# Cuttomized_Industrial_controller.net
KiCad netlist of a schematic drawn in Altium Designer
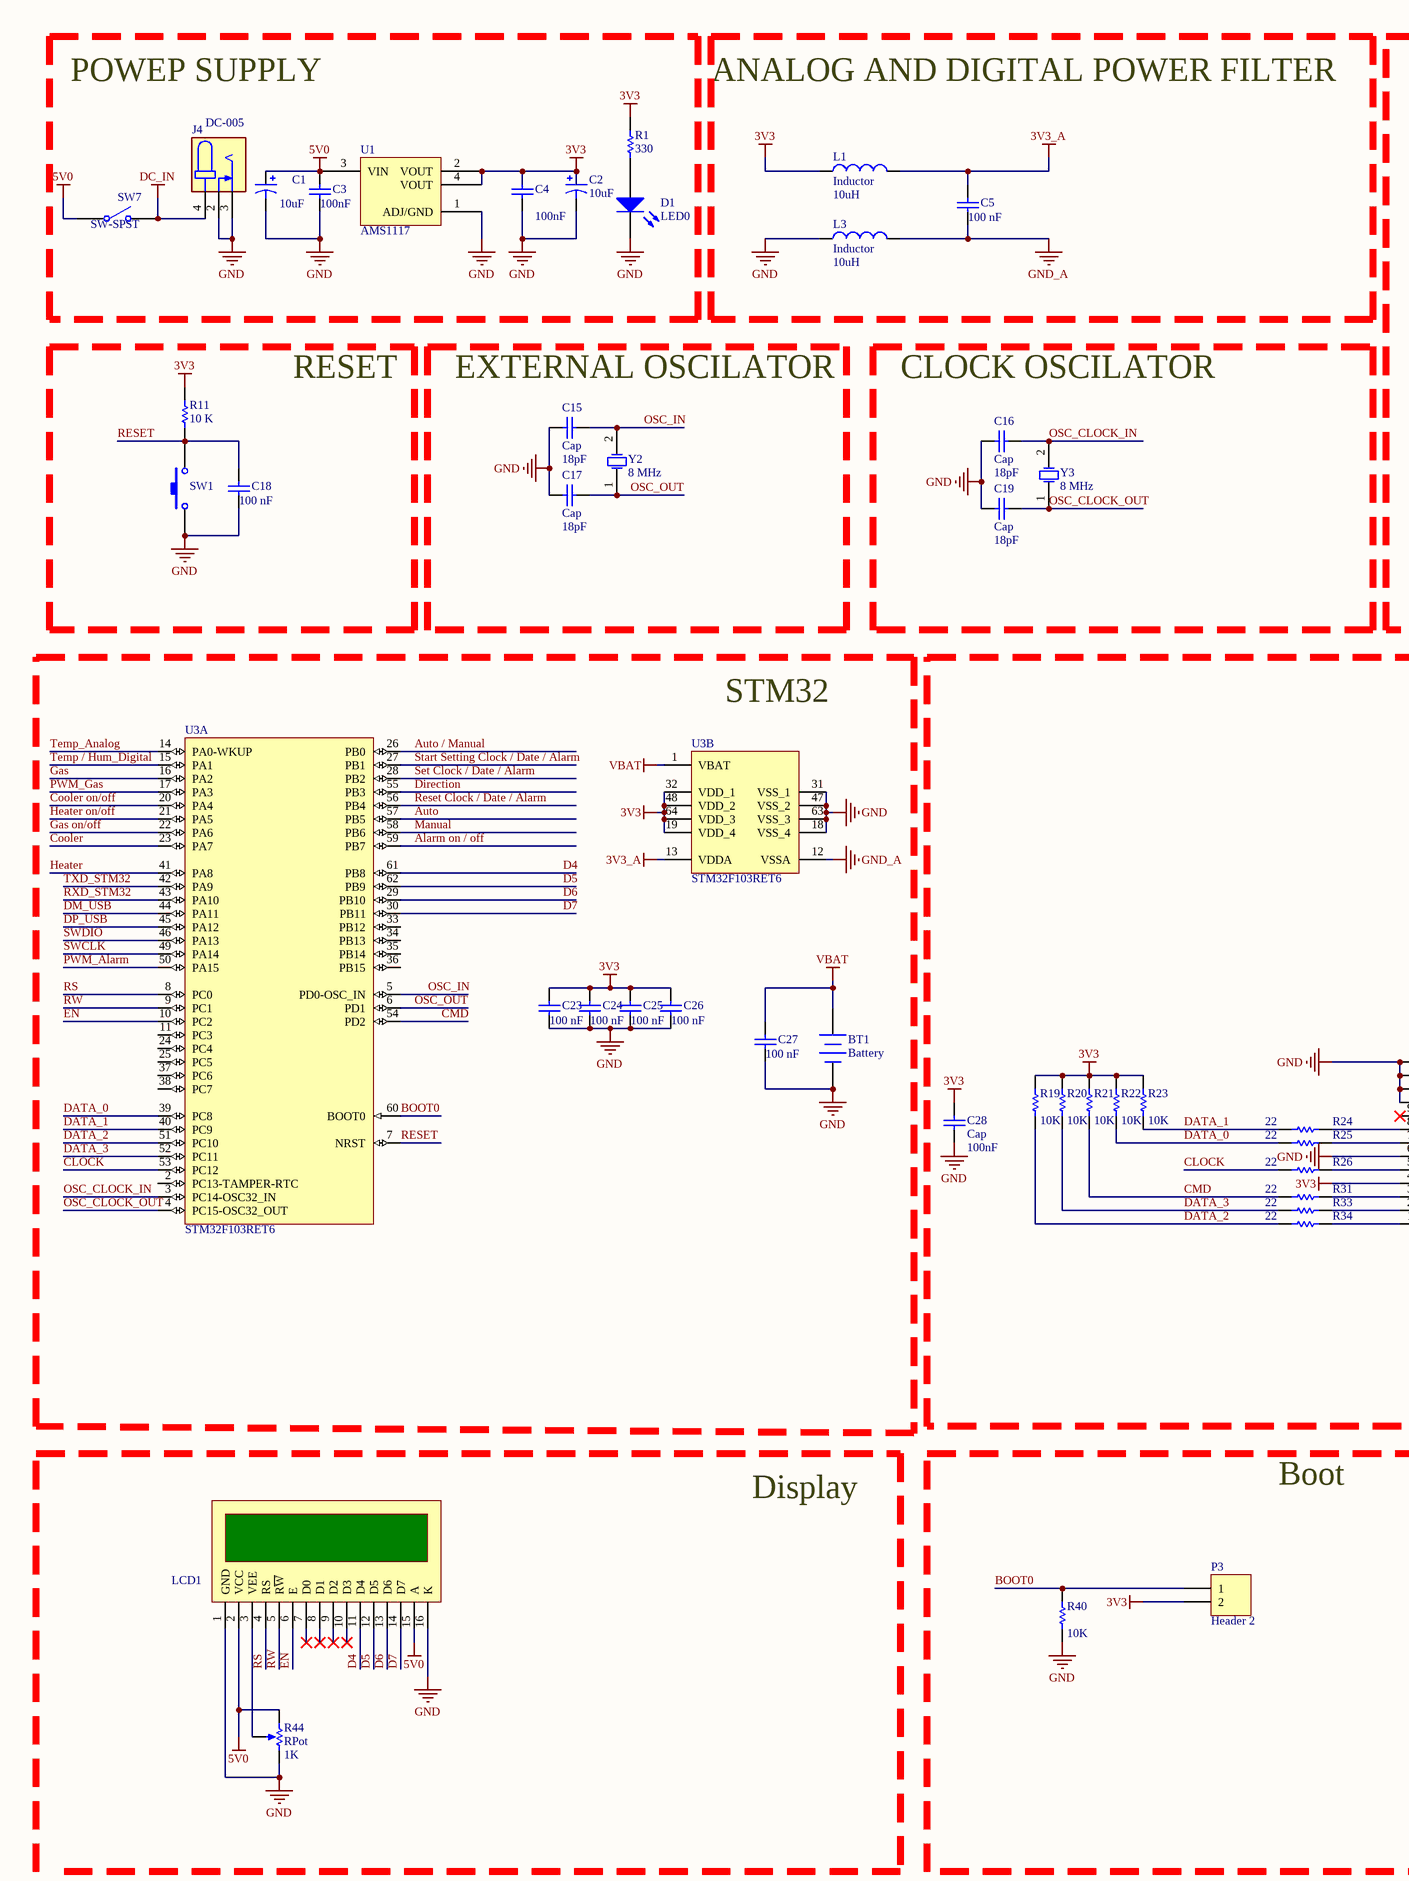
[diagram p0: Cuttomized_Industrial_controller.SchDoc, left]
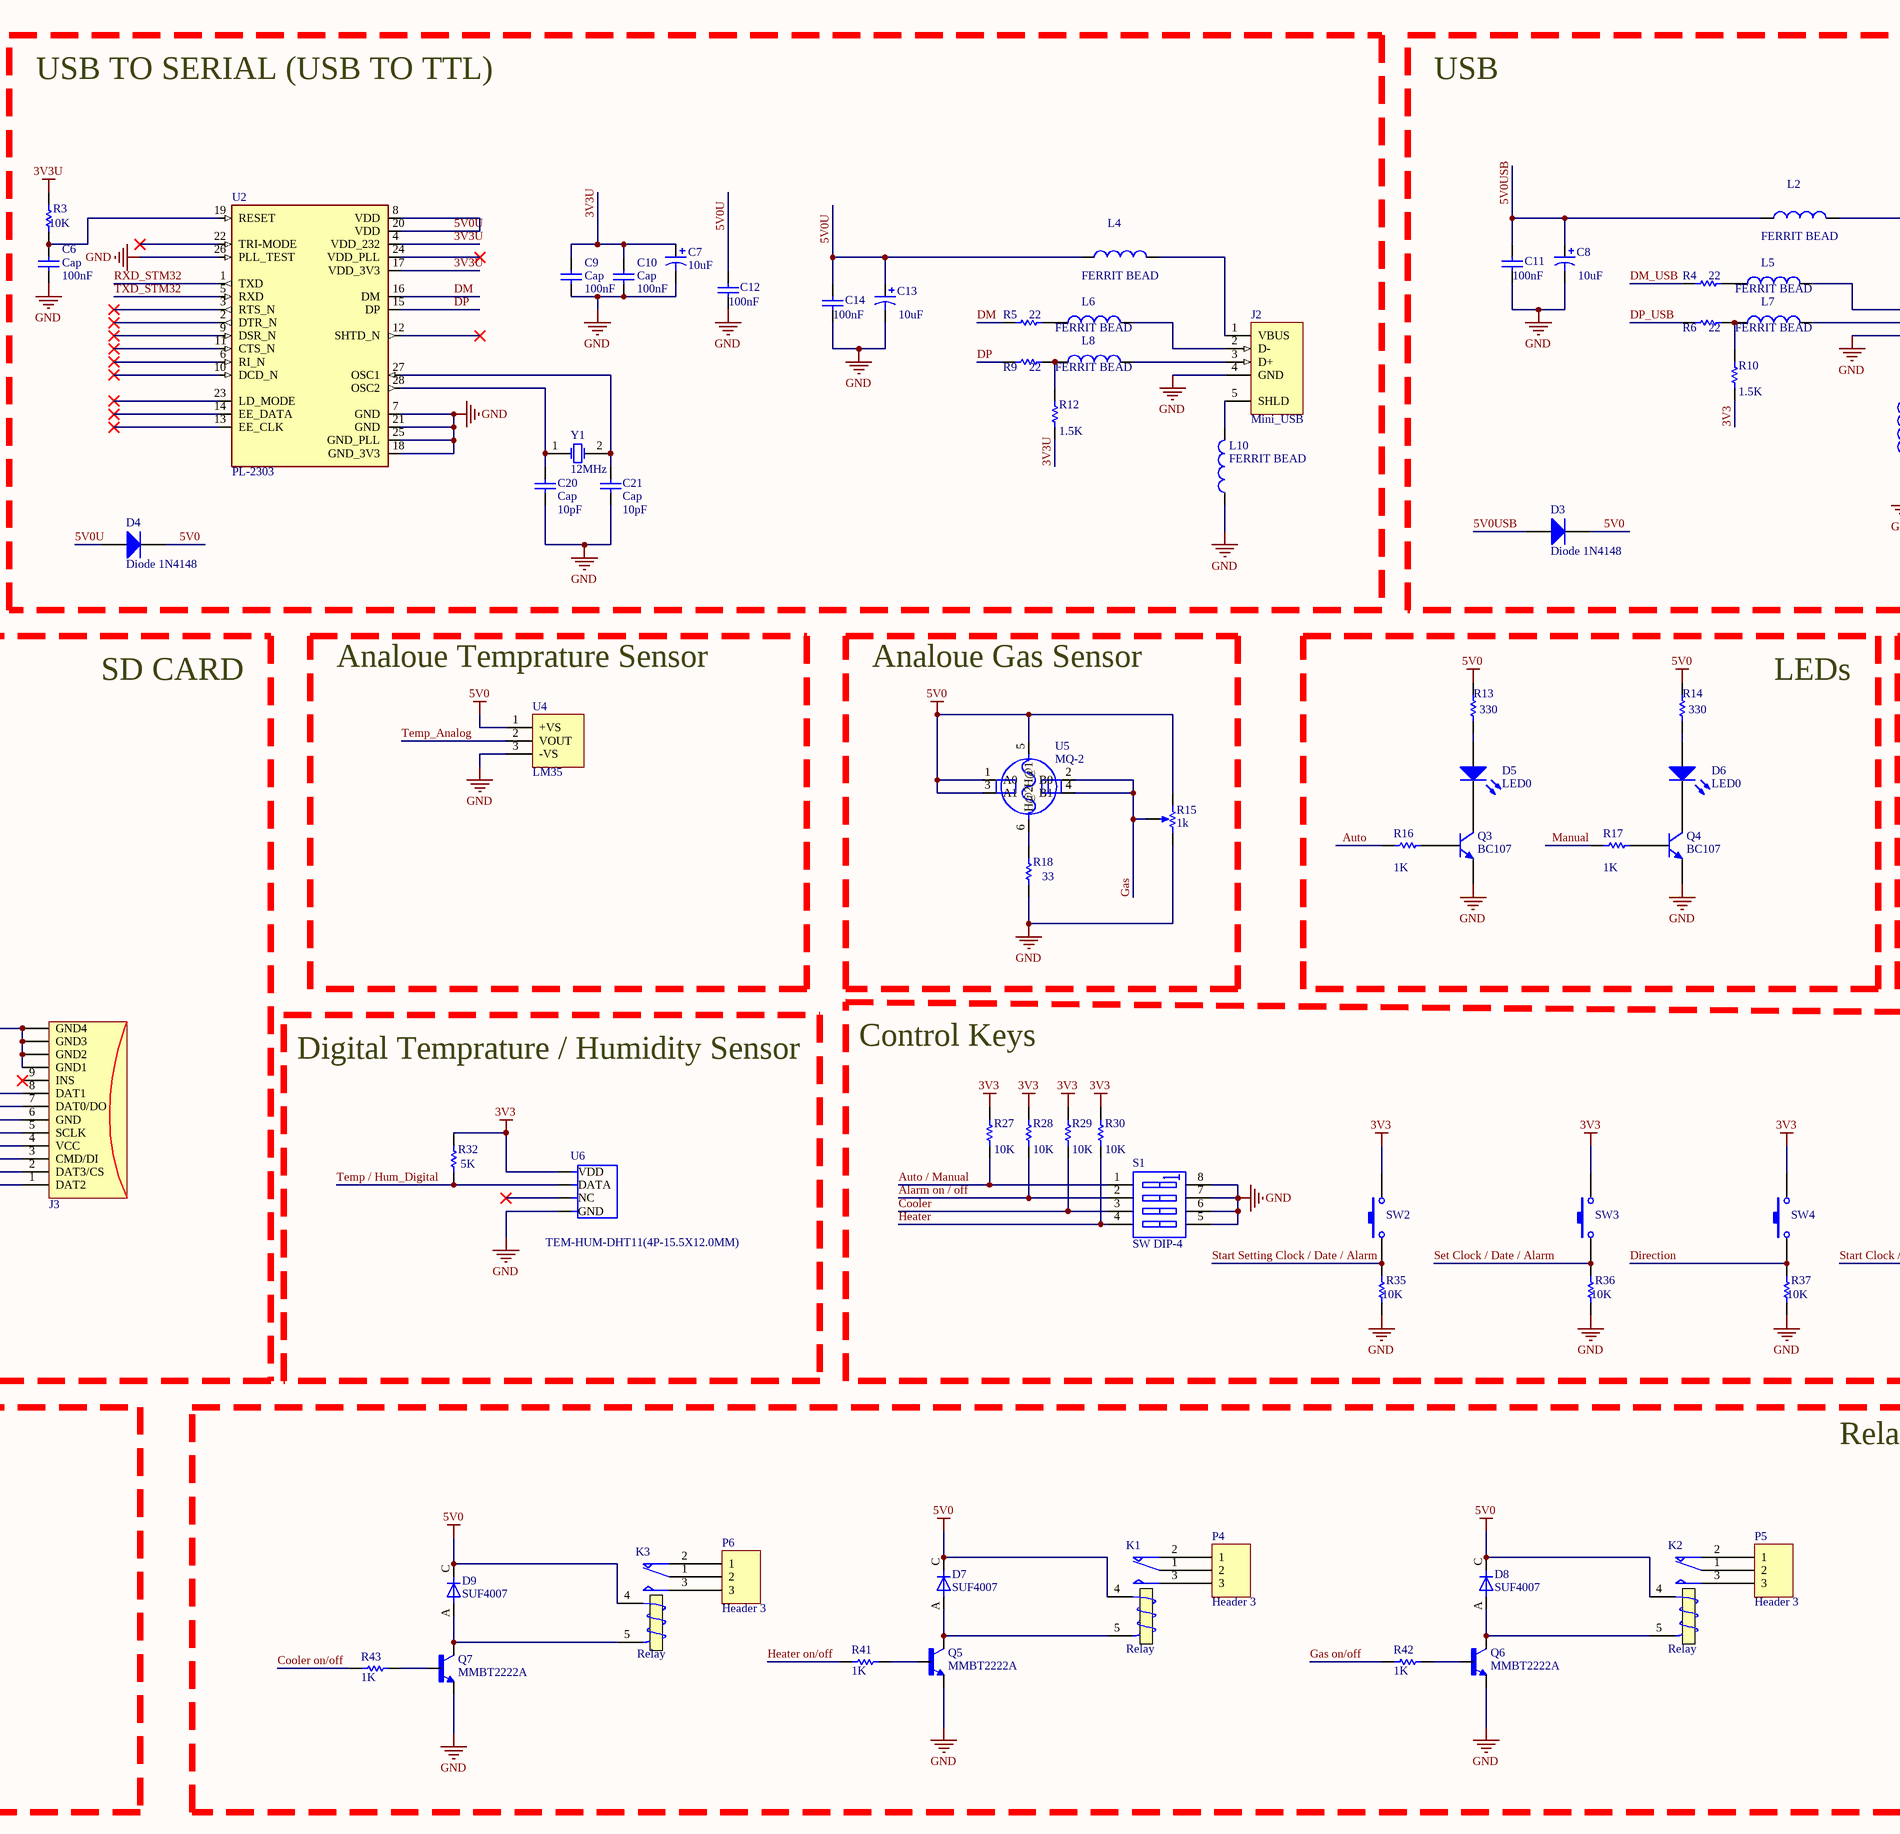
[diagram p1: Cuttomized_Industrial_controller.SchDoc, middle]
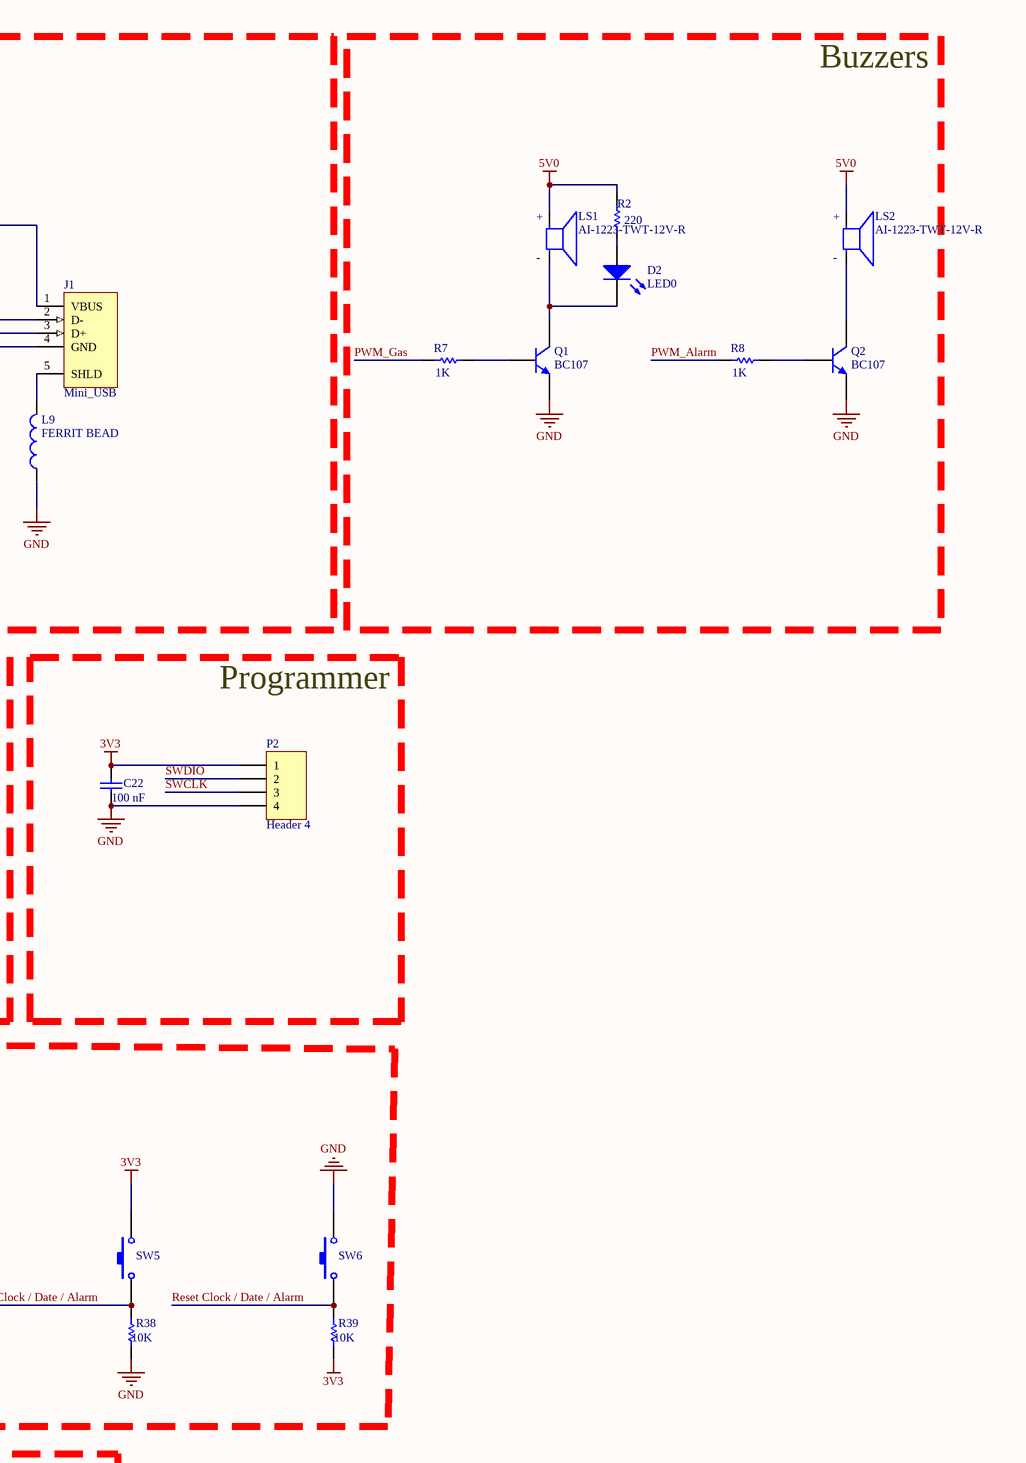
[diagram p2: Cuttomized_Industrial_controller.SchDoc, right]

(export (version "E")
  (design (tool "Eeschema 10.0.6"))
  (components
    (comp (ref "BT1")
      (value "Battery")
      (footprint "BAT-2")
      (description "Multicell Battery")
      (fields (field (name "PUBLISHER") "Altium Limited"))
      (libsource (lib "Miscellaneous Devices") (part "Battery"))
    )
    (comp (ref "C1")
      (value "10uF")
      (footprint "CAP_tantal")
      (description "Capacitor")
      (libsource (lib "My_LIB") (part "Cap Elec"))
    )
    (comp (ref "C2")
      (value "10uF")
      (footprint "CAP_tantal")
      (description "Capacitor")
      (libsource (lib "") (part "Cap Elec_1"))
    )
    (comp (ref "C3")
      (value "100nF")
      (footprint "C0805")
      (description "Capacitor (Semiconductor SIM Model)")
      (fields (field (name "PUBLISHER") "Altium Limited"))
      (libsource (lib "Miscellaneous Devices") (part "Cap Semi"))
    )
    (comp (ref "C4")
      (value "100nF")
      (footprint "C0805")
      (description "Capacitor (Semiconductor SIM Model)")
      (fields (field (name "PUBLISHER") "Altium Limited"))
      (libsource (lib "Miscellaneous Devices") (part "Cap Semi"))
    )
    (comp (ref "C5")
      (value "100 nF")
      (footprint "C0805")
      (description "Capacitor (Semiconductor SIM Model)")
      (fields (field (name "PUBLISHER") "Altium Limited"))
      (libsource (lib "Miscellaneous Devices") (part "Cap Semi"))
    )
    (comp (ref "C6")
      (value "Cap")
      (footprint "C0805")
      (description "Capacitor")
      (fields (field (name "ALTIUM_VALUE") "100nF") (field (name "PUBLISHER") "Altium Limited"))
      (libsource (lib "Miscellaneous Devices") (part "Cap"))
    )
    (comp (ref "C7")
      (value "10uF")
      (footprint "CAP_tantal")
      (description "Capacitor")
      (libsource (lib "My_LIB") (part "Cap Elec"))
    )
    (comp (ref "C8")
      (value "10uF")
      (footprint "CAP_tantal")
      (description "Capacitor")
      (libsource (lib "My_LIB") (part "Cap Elec"))
    )
    (comp (ref "C9")
      (value "Cap")
      (footprint "C0805")
      (description "Capacitor")
      (fields (field (name "ALTIUM_VALUE") "100nF") (field (name "PUBLISHER") "Altium Limited"))
      (libsource (lib "Miscellaneous Devices") (part "Cap"))
    )
    (comp (ref "C10")
      (value "Cap")
      (footprint "C0805")
      (description "Capacitor")
      (fields (field (name "ALTIUM_VALUE") "100nF") (field (name "PUBLISHER") "Altium Limited"))
      (libsource (lib "Miscellaneous Devices") (part "Cap"))
    )
    (comp (ref "C11")
      (value "100nF")
      (footprint "C0805")
      (description "Capacitor")
      (fields (field (name "PUBLISHER") "Altium Limited"))
      (libsource (lib "Miscellaneous Devices") (part "Cap"))
    )
    (comp (ref "C12")
      (value "100nF")
      (footprint "C0805")
      (description "Capacitor")
      (fields (field (name "PUBLISHER") "Altium Limited"))
      (libsource (lib "Miscellaneous Devices") (part "Cap"))
    )
    (comp (ref "C13")
      (value "10uF")
      (footprint "CAP_tantal")
      (description "Capacitor")
      (libsource (lib "My_LIB") (part "Cap Elec"))
    )
    (comp (ref "C14")
      (value "100nF")
      (footprint "C0805")
      (description "Capacitor")
      (fields (field (name "PUBLISHER") "Altium Limited"))
      (libsource (lib "Miscellaneous Devices") (part "Cap"))
    )
    (comp (ref "C15")
      (value "Cap")
      (footprint "C0805")
      (description "Capacitor")
      (fields (field (name "ALTIUM_VALUE") "18pF") (field (name "PUBLISHER") "Altium Limited"))
      (libsource (lib "Miscellaneous Devices") (part "Cap"))
    )
    (comp (ref "C16")
      (value "Cap")
      (footprint "C0805")
      (description "Capacitor")
      (fields (field (name "ALTIUM_VALUE") "18pF") (field (name "PUBLISHER") "Altium Limited"))
      (libsource (lib "Miscellaneous Devices") (part "Cap"))
    )
    (comp (ref "C17")
      (value "Cap")
      (footprint "C0805")
      (description "Capacitor")
      (fields (field (name "ALTIUM_VALUE") "18pF") (field (name "PUBLISHER") "Altium Limited"))
      (libsource (lib "Miscellaneous Devices") (part "Cap"))
    )
    (comp (ref "C18")
      (value "100 nF")
      (footprint "C0805")
      (description "Capacitor")
      (fields (field (name "PUBLISHER") "Altium Limited"))
      (libsource (lib "Miscellaneous Devices") (part "Cap"))
    )
    (comp (ref "C19")
      (value "Cap")
      (footprint "C0805")
      (description "Capacitor")
      (fields (field (name "ALTIUM_VALUE") "18pF") (field (name "PUBLISHER") "Altium Limited"))
      (libsource (lib "Miscellaneous Devices") (part "Cap"))
    )
    (comp (ref "C20")
      (value "Cap")
      (footprint "C0805")
      (description "Capacitor")
      (fields (field (name "ALTIUM_VALUE") "10pF") (field (name "PUBLISHER") "Altium Limited"))
      (libsource (lib "Miscellaneous Devices") (part "Cap"))
    )
    (comp (ref "C21")
      (value "Cap")
      (footprint "C0805")
      (description "Capacitor")
      (fields (field (name "ALTIUM_VALUE") "10pF") (field (name "PUBLISHER") "Altium Limited"))
      (libsource (lib "Miscellaneous Devices") (part "Cap"))
    )
    (comp (ref "C22")
      (value "100 nF")
      (footprint "C0805")
      (description "Capacitor")
      (fields (field (name "PUBLISHER") "Altium Limited"))
      (libsource (lib "Miscellaneous Devices") (part "Cap"))
    )
    (comp (ref "C23")
      (value "100 nF")
      (footprint "C0805")
      (description "Capacitor")
      (fields (field (name "PUBLISHER") "Altium Limited"))
      (libsource (lib "Miscellaneous Devices") (part "Cap"))
    )
    (comp (ref "C24")
      (value "100 nF")
      (footprint "C0805")
      (description "Capacitor")
      (fields (field (name "PUBLISHER") "Altium Limited"))
      (libsource (lib "Miscellaneous Devices") (part "Cap"))
    )
    (comp (ref "C25")
      (value "100 nF")
      (footprint "C0805")
      (description "Capacitor")
      (fields (field (name "PUBLISHER") "Altium Limited"))
      (libsource (lib "Miscellaneous Devices") (part "Cap"))
    )
    (comp (ref "C26")
      (value "100 nF")
      (footprint "C0805")
      (description "Capacitor")
      (fields (field (name "PUBLISHER") "Altium Limited"))
      (libsource (lib "Miscellaneous Devices") (part "Cap"))
    )
    (comp (ref "C27")
      (value "100 nF")
      (footprint "C0805")
      (description "Capacitor")
      (fields (field (name "PUBLISHER") "Altium Limited"))
      (libsource (lib "Miscellaneous Devices") (part "Cap"))
    )
    (comp (ref "C28")
      (value "Cap")
      (footprint "C0805")
      (description "Capacitor")
      (fields (field (name "ALTIUM_VALUE") "100nF") (field (name "PUBLISHER") "Altium Limited"))
      (libsource (lib "Miscellaneous Devices") (part "Cap"))
    )
    (comp (ref "D1")
      (value "LED0")
      (footprint "C0805")
      (description "Typical INFRARED GaAs LED")
      (fields (field (name "PUBLISHER") "Altium Limited"))
      (libsource (lib "Miscellaneous Devices") (part "LED0"))
    )
    (comp (ref "D2")
      (value "LED0")
      (footprint "C0805")
      (description "Typical INFRARED GaAs LED")
      (fields (field (name "PUBLISHER") "Altium Limited"))
      (libsource (lib "Miscellaneous Devices") (part "LED0"))
    )
    (comp (ref "D3")
      (value "Diode 1N4148")
      (footprint "SOD-123")
      (description "High Conductance Fast Diode")
      (fields (field (name "PUBLISHER") "Altium Limited"))
      (libsource (lib "Miscellaneous Devices") (part "Diode 1N4148"))
    )
    (comp (ref "D4")
      (value "Diode 1N4148")
      (footprint "SOD-123")
      (description "High Conductance Fast Diode")
      (fields (field (name "PUBLISHER") "Altium Limited"))
      (libsource (lib "Miscellaneous Devices") (part "Diode 1N4148"))
    )
    (comp (ref "D5")
      (value "LED0")
      (footprint "C0805")
      (description "Typical INFRARED GaAs LED")
      (fields (field (name "PUBLISHER") "Altium Limited"))
      (libsource (lib "Miscellaneous Devices") (part "LED0"))
    )
    (comp (ref "D6")
      (value "LED0")
      (footprint "C0805")
      (description "Typical INFRARED GaAs LED")
      (fields (field (name "PUBLISHER") "Altium Limited"))
      (libsource (lib "Miscellaneous Devices") (part "LED0"))
    )
    (comp (ref "D7")
      (value "SUF4007")
      (footprint "DIOMELF5025N")
      (description "Diode Switching 1KV 1A Automotive 2-Pin MELF")
      (fields (field (name "MF") "Diotec"))
      (libsource (lib "SUF4007") (part "SUF4007"))
    )
    (comp (ref "D8")
      (value "SUF4007")
      (footprint "DIOMELF5025N")
      (description "Diode Switching 1KV 1A Automotive 2-Pin MELF")
      (fields (field (name "MF") "Diotec"))
      (libsource (lib "SUF4007") (part "SUF4007"))
    )
    (comp (ref "D9")
      (value "SUF4007")
      (footprint "DIOMELF5025N")
      (description "Diode Switching 1KV 1A Automotive 2-Pin MELF")
      (fields (field (name "MF") "Diotec"))
      (libsource (lib "SUF4007") (part "SUF4007"))
    )
    (comp (ref "J1")
      (value "Mini_USB")
      (footprint "USB_mini")
      (description "USB 2.0, Right Angle, SMT, B Type, Receptacle, 5 Position, Black")
      (fields (field (name "PUBLISHER") "Altium Limited"))
      (libsource (lib "My_LIB") (part "USB_Mini"))
    )
    (comp (ref "J2")
      (value "Mini_USB")
      (footprint "USB_mini")
      (description "USB 2.0, Right Angle, SMT, B Type, Receptacle, 5 Position, Black")
      (fields (field (name "PUBLISHER") "Altium Limited"))
      (libsource (lib "My_LIB") (part "USB_Mini"))
    )
    (comp (ref "J3")
      (value "MMC-uSD")
      (footprint "SD-MicroSD_1")
      (description "uSD/MMC Socket")
      (libsource (lib "My_LIB") (part "MMC-uSD"))
    )
    (comp (ref "J4")
      (value "DC-005")
      (footprint "NINIGI_DC-005")
      (description "DC Jack")
      (libsource (lib "DC-005") (part "DC-005"))
    )
    (comp (ref "K1")
      (value "Relay")
      (footprint "Relay 5A")
      (description "SPDT Relay")
      (fields (field (name "PUBLISHER") "Altium Limited"))
      (libsource (lib "Miscellaneous Devices") (part "Relay"))
    )
    (comp (ref "K2")
      (value "Relay")
      (footprint "Relay 5A")
      (description "SPDT Relay")
      (fields (field (name "PUBLISHER") "Altium Limited"))
      (libsource (lib "Miscellaneous Devices") (part "Relay"))
    )
    (comp (ref "K3")
      (value "Relay")
      (footprint "Relay 5A")
      (description "SPDT Relay")
      (fields (field (name "PUBLISHER") "Altium Limited"))
      (libsource (lib "Miscellaneous Devices") (part "Relay"))
    )
    (comp (ref "L1")
      (value "Inductor")
      (footprint "C0805")
      (fields (field (name "ALTIUM_VALUE") "10uH") (field (name "PUBLISHER") "Altium Limited"))
      (libsource (lib "Miscellaneous Devices") (part "Inductor"))
    )
    (comp (ref "L2")
      (value "FERRIT BEAD")
      (footprint "C0805")
      (description "Inductor")
      (fields (field (name "PUBLISHER") "Altium Limited"))
      (libsource (lib "Miscellaneous Devices") (part "Inductor"))
    )
    (comp (ref "L3")
      (value "Inductor")
      (footprint "C0805")
      (fields (field (name "ALTIUM_VALUE") "10uH") (field (name "PUBLISHER") "Altium Limited"))
      (libsource (lib "Miscellaneous Devices") (part "Inductor"))
    )
    (comp (ref "L4")
      (value "FERRIT BEAD")
      (footprint "C0805")
      (description "Inductor")
      (fields (field (name "PUBLISHER") "Altium Limited"))
      (libsource (lib "Miscellaneous Devices") (part "Inductor"))
    )
    (comp (ref "L5")
      (value "FERRIT BEAD")
      (footprint "C0805")
      (description "Inductor")
      (fields (field (name "PUBLISHER") "Altium Limited"))
      (libsource (lib "Miscellaneous Devices") (part "Inductor"))
    )
    (comp (ref "L6")
      (value "FERRIT BEAD")
      (footprint "C0805")
      (description "Inductor")
      (fields (field (name "PUBLISHER") "Altium Limited"))
      (libsource (lib "Miscellaneous Devices") (part "Inductor"))
    )
    (comp (ref "L7")
      (value "FERRIT BEAD")
      (footprint "C0805")
      (description "Inductor")
      (fields (field (name "PUBLISHER") "Altium Limited"))
      (libsource (lib "Miscellaneous Devices") (part "Inductor"))
    )
    (comp (ref "L8")
      (value "FERRIT BEAD")
      (footprint "C0805")
      (description "Inductor")
      (fields (field (name "PUBLISHER") "Altium Limited"))
      (libsource (lib "Miscellaneous Devices") (part "Inductor"))
    )
    (comp (ref "L9")
      (value "FERRIT BEAD")
      (footprint "C0805")
      (description "Inductor")
      (fields (field (name "PUBLISHER") "Altium Limited"))
      (libsource (lib "Miscellaneous Devices") (part "Inductor"))
    )
    (comp (ref "L10")
      (value "FERRIT BEAD")
      (footprint "C0805")
      (description "Inductor")
      (fields (field (name "PUBLISHER") "Altium Limited"))
      (libsource (lib "Miscellaneous Devices") (part "Inductor"))
    )
    (comp (ref "LCD1") (value "LCD2x16") (footprint "LCD 2*16") (libsource (lib "My_LIB") (part "LCD2x16")))
    (comp (ref "LS1")
      (value "AI-1223-TWT-12V-R")
      (footprint "XDCR_AI-1223-TWT-12V-R:XDCR_AI-1223-TWT-12V-R")
      (description "ELECTRO-MECHANICAL AUDIO INDICATOR")
      (fields (field (name "MF") "PUI Audio,"))
      (libsource (lib "AI-1223-TWT-12V-R") (part "AI-1223-TWT-12V-R"))
    )
    (comp (ref "LS2")
      (value "AI-1223-TWT-12V-R")
      (footprint "XDCR_AI-1223-TWT-12V-R:XDCR_AI-1223-TWT-12V-R")
      (description "ELECTRO-MECHANICAL AUDIO INDICATOR")
      (fields (field (name "MF") "PUI Audio,"))
      (libsource (lib "AI-1223-TWT-12V-R") (part "AI-1223-TWT-12V-R"))
    )
    (comp (ref "P2")
      (value "Header 4")
      (footprint "HDR1X4")
      (description "Header, 4-Pin")
      (fields (field (name "PUBLISHER") "Altium Limited"))
      (libsource (lib "Miscellaneous Connectors") (part "Header 4"))
    )
    (comp (ref "P3")
      (value "Header 2")
      (footprint "HDR1X2")
      (description "Header, 2-Pin")
      (fields (field (name "PUBLISHER") "Altium Limited"))
      (libsource (lib "Miscellaneous Connectors") (part "Header 2"))
    )
    (comp (ref "P4")
      (value "Header 3")
      (footprint "Connectors:phoenix terminal 3")
      (description "Header, 3-Pin")
      (fields (field (name "PUBLISHER") "Altium Limited"))
      (libsource (lib "Miscellaneous Connectors") (part "Header 3"))
    )
    (comp (ref "P5")
      (value "Header 3")
      (footprint "Connectors:phoenix terminal 3")
      (description "Header, 3-Pin")
      (fields (field (name "PUBLISHER") "Altium Limited"))
      (libsource (lib "Miscellaneous Connectors") (part "Header 3"))
    )
    (comp (ref "P6")
      (value "Header 3")
      (footprint "Connectors:phoenix terminal 3")
      (description "Header, 3-Pin")
      (fields (field (name "PUBLISHER") "Altium Limited"))
      (libsource (lib "Miscellaneous Connectors") (part "Header 3"))
    )
    (comp (ref "Q1") (value "BC107") (footprint "SOT23") (libsource (lib "My_LIB") (part "BC107")))
    (comp (ref "Q2") (value "BC107") (footprint "MMBT2222A:SOT23") (libsource (lib "My_LIB") (part "BC107")))
    (comp (ref "Q3") (value "BC107") (footprint "SOT23") (libsource (lib "My_LIB") (part "BC107")))
    (comp (ref "Q4") (value "BC107") (footprint "SOT23") (libsource (lib "My_LIB") (part "BC107")))
    (comp (ref "Q5")
      (value "MMBT2222A")
      (footprint "SOT23")
      (description "Bipolar _BJT_ Transistor NPN 40V 600mA 270MHz 350mW Surface Mount SOT-23-3")
      (fields (field (name "MF") "STMicroelectronics"))
      (libsource (lib "MMBT2222A") (part "MMBT2222A"))
    )
    (comp (ref "Q6")
      (value "MMBT2222A")
      (footprint "SOT23")
      (description "Bipolar _BJT_ Transistor NPN 40V 600mA 270MHz 350mW Surface Mount SOT-23-3")
      (fields (field (name "MF") "STMicroelectronics"))
      (libsource (lib "MMBT2222A") (part "MMBT2222A"))
    )
    (comp (ref "Q7")
      (value "MMBT2222A")
      (footprint "SOT23")
      (description "Bipolar _BJT_ Transistor NPN 40V 600mA 270MHz 350mW Surface Mount SOT-23-3")
      (fields (field (name "MF") "STMicroelectronics"))
      (libsource (lib "MMBT2222A") (part "MMBT2222A"))
    )
    (comp (ref "R1") (value "330") (footprint "C0805") (libsource (lib "My_LIB") (part "RES")))
    (comp (ref "R2")
      (value "220")
      (footprint "C0805")
      (description "Semiconductor Resistor")
      (fields (field (name "PUBLISHER") "Altium Limited"))
      (libsource (lib "Miscellaneous Devices") (part "Res Semi"))
    )
    (comp (ref "R3")
      (value "10K")
      (footprint "C0805")
      (description "Semiconductor Resistor")
      (fields (field (name "PUBLISHER") "Altium Limited"))
      (libsource (lib "Miscellaneous Devices") (part "Res Semi"))
    )
    (comp (ref "R4")
      (value "22")
      (footprint "C0805")
      (description "Semiconductor Resistor")
      (fields (field (name "PUBLISHER") "Altium Limited"))
      (libsource (lib "Miscellaneous Devices") (part "Res Semi"))
    )
    (comp (ref "R5")
      (value "22")
      (footprint "C0805")
      (description "Semiconductor Resistor")
      (fields (field (name "PUBLISHER") "Altium Limited"))
      (libsource (lib "Miscellaneous Devices") (part "Res Semi"))
    )
    (comp (ref "R6")
      (value "22")
      (footprint "C0805")
      (description "Semiconductor Resistor")
      (fields (field (name "PUBLISHER") "Altium Limited"))
      (libsource (lib "Miscellaneous Devices") (part "Res Semi"))
    )
    (comp (ref "R7")
      (value "1K")
      (footprint "C0805")
      (description "Semiconductor Resistor")
      (fields (field (name "PUBLISHER") "Altium Limited"))
      (libsource (lib "Miscellaneous Devices") (part "Res Semi"))
    )
    (comp (ref "R8")
      (value "1K")
      (footprint "C0805")
      (description "Semiconductor Resistor")
      (fields (field (name "PUBLISHER") "Altium Limited"))
      (libsource (lib "Miscellaneous Devices") (part "Res Semi"))
    )
    (comp (ref "R9")
      (value "22")
      (footprint "C0805")
      (description "Semiconductor Resistor")
      (fields (field (name "PUBLISHER") "Altium Limited"))
      (libsource (lib "Miscellaneous Devices") (part "Res Semi"))
    )
    (comp (ref "R10")
      (value "1.5K")
      (footprint "C0805")
      (description "Semiconductor Resistor")
      (fields (field (name "PUBLISHER") "Altium Limited"))
      (libsource (lib "Miscellaneous Devices") (part "Res Semi"))
    )
    (comp (ref "R11") (value "10 K") (footprint "C0805") (libsource (lib "My_LIB") (part "RES")))
    (comp (ref "R12")
      (value "1.5K")
      (footprint "C0805")
      (description "Semiconductor Resistor")
      (fields (field (name "PUBLISHER") "Altium Limited"))
      (libsource (lib "Miscellaneous Devices") (part "Res Semi"))
    )
    (comp (ref "R13")
      (value "330")
      (footprint "C0805")
      (description "Semiconductor Resistor")
      (fields (field (name "PUBLISHER") "Altium Limited"))
      (libsource (lib "Miscellaneous Devices") (part "Res Semi"))
    )
    (comp (ref "R14")
      (value "330")
      (footprint "C0805")
      (description "Semiconductor Resistor")
      (fields (field (name "PUBLISHER") "Altium Limited"))
      (libsource (lib "Miscellaneous Devices") (part "Res Semi"))
    )
    (comp (ref "R15")
      (value "1k")
      (footprint "Multi-Turn")
      (description "Potentiometer")
      (libsource (lib "My_LIB") (part "POT"))
    )
    (comp (ref "R16")
      (value "1K")
      (footprint "C0805")
      (description "Semiconductor Resistor")
      (fields (field (name "PUBLISHER") "Altium Limited"))
      (libsource (lib "Miscellaneous Devices") (part "Res Semi"))
    )
    (comp (ref "R17")
      (value "1K")
      (footprint "C0805")
      (description "Semiconductor Resistor")
      (fields (field (name "PUBLISHER") "Altium Limited"))
      (libsource (lib "Miscellaneous Devices") (part "Res Semi"))
    )
    (comp (ref "R18")
      (value "33")
      (footprint "C0805")
      (description "Semiconductor Resistor")
      (fields (field (name "PUBLISHER") "Altium Limited"))
      (libsource (lib "Miscellaneous Devices") (part "Res Semi"))
    )
    (comp (ref "R19")
      (value "10K")
      (footprint "C0805")
      (description "Semiconductor Resistor")
      (fields (field (name "PUBLISHER") "Altium Limited"))
      (libsource (lib "Miscellaneous Devices") (part "Res Semi"))
    )
    (comp (ref "R20")
      (value "10K")
      (footprint "C0805")
      (description "Semiconductor Resistor")
      (fields (field (name "PUBLISHER") "Altium Limited"))
      (libsource (lib "Miscellaneous Devices") (part "Res Semi"))
    )
    (comp (ref "R21")
      (value "10K")
      (footprint "C0805")
      (description "Semiconductor Resistor")
      (fields (field (name "PUBLISHER") "Altium Limited"))
      (libsource (lib "Miscellaneous Devices") (part "Res Semi"))
    )
    (comp (ref "R22")
      (value "10K")
      (footprint "C0805")
      (description "Semiconductor Resistor")
      (fields (field (name "PUBLISHER") "Altium Limited"))
      (libsource (lib "Miscellaneous Devices") (part "Res Semi"))
    )
    (comp (ref "R23")
      (value "10K")
      (footprint "C0805")
      (description "Semiconductor Resistor")
      (fields (field (name "PUBLISHER") "Altium Limited"))
      (libsource (lib "Miscellaneous Devices") (part "Res Semi"))
    )
    (comp (ref "R24")
      (value "22")
      (footprint "C0805")
      (description "Semiconductor Resistor")
      (fields (field (name "PUBLISHER") "Altium Limited"))
      (libsource (lib "Miscellaneous Devices") (part "Res Semi"))
    )
    (comp (ref "R25")
      (value "22")
      (footprint "C0805")
      (description "Semiconductor Resistor")
      (fields (field (name "PUBLISHER") "Altium Limited"))
      (libsource (lib "Miscellaneous Devices") (part "Res Semi"))
    )
    (comp (ref "R26")
      (value "22")
      (footprint "C0805")
      (description "Semiconductor Resistor")
      (fields (field (name "PUBLISHER") "Altium Limited"))
      (libsource (lib "Miscellaneous Devices") (part "Res Semi"))
    )
    (comp (ref "R27")
      (value "10K")
      (footprint "C0805")
      (description "Semiconductor Resistor")
      (fields (field (name "PUBLISHER") "Altium Limited"))
      (libsource (lib "Miscellaneous Devices") (part "Res Semi"))
    )
    (comp (ref "R28")
      (value "10K")
      (footprint "C0805")
      (description "Semiconductor Resistor")
      (fields (field (name "PUBLISHER") "Altium Limited"))
      (libsource (lib "Miscellaneous Devices") (part "Res Semi"))
    )
    (comp (ref "R29")
      (value "10K")
      (footprint "C0805")
      (description "Semiconductor Resistor")
      (fields (field (name "PUBLISHER") "Altium Limited"))
      (libsource (lib "Miscellaneous Devices") (part "Res Semi"))
    )
    (comp (ref "R30")
      (value "10K")
      (footprint "C0805")
      (description "Semiconductor Resistor")
      (fields (field (name "PUBLISHER") "Altium Limited"))
      (libsource (lib "Miscellaneous Devices") (part "Res Semi"))
    )
    (comp (ref "R31")
      (value "22")
      (footprint "C0805")
      (description "Semiconductor Resistor")
      (fields (field (name "PUBLISHER") "Altium Limited"))
      (libsource (lib "Miscellaneous Devices") (part "Res Semi"))
    )
    (comp (ref "R32")
      (value "5K")
      (footprint "C0805")
      (description "Semiconductor Resistor")
      (fields (field (name "PUBLISHER") "Altium Limited"))
      (libsource (lib "Miscellaneous Devices") (part "Res Semi"))
    )
    (comp (ref "R33")
      (value "22")
      (footprint "C0805")
      (description "Semiconductor Resistor")
      (fields (field (name "PUBLISHER") "Altium Limited"))
      (libsource (lib "Miscellaneous Devices") (part "Res Semi"))
    )
    (comp (ref "R34")
      (value "22")
      (footprint "C0805")
      (description "Semiconductor Resistor")
      (fields (field (name "PUBLISHER") "Altium Limited"))
      (libsource (lib "Miscellaneous Devices") (part "Res Semi"))
    )
    (comp (ref "R35")
      (value "10K")
      (footprint "C0805")
      (description "Semiconductor Resistor")
      (fields (field (name "PUBLISHER") "Altium Limited"))
      (libsource (lib "Miscellaneous Devices") (part "Res Semi"))
    )
    (comp (ref "R36")
      (value "10K")
      (footprint "C0805")
      (description "Semiconductor Resistor")
      (fields (field (name "PUBLISHER") "Altium Limited"))
      (libsource (lib "Miscellaneous Devices") (part "Res Semi"))
    )
    (comp (ref "R37")
      (value "10K")
      (footprint "C0805")
      (description "Semiconductor Resistor")
      (fields (field (name "PUBLISHER") "Altium Limited"))
      (libsource (lib "Miscellaneous Devices") (part "Res Semi"))
    )
    (comp (ref "R38")
      (value "10K")
      (footprint "C0805")
      (description "Semiconductor Resistor")
      (fields (field (name "PUBLISHER") "Altium Limited"))
      (libsource (lib "Miscellaneous Devices") (part "Res Semi"))
    )
    (comp (ref "R39")
      (value "10K")
      (footprint "C0805")
      (description "Semiconductor Resistor")
      (fields (field (name "PUBLISHER") "Altium Limited"))
      (libsource (lib "Miscellaneous Devices") (part "Res Semi"))
    )
    (comp (ref "R40")
      (value "10K")
      (footprint "C0805")
      (description "Semiconductor Resistor")
      (fields (field (name "PUBLISHER") "Altium Limited"))
      (libsource (lib "Miscellaneous Devices") (part "Res Semi"))
    )
    (comp (ref "R41")
      (value "1K")
      (footprint "C0805")
      (description "Semiconductor Resistor")
      (fields (field (name "PUBLISHER") "Altium Limited"))
      (libsource (lib "Miscellaneous Devices") (part "Res Semi"))
    )
    (comp (ref "R42")
      (value "1K")
      (footprint "C0805")
      (description "Semiconductor Resistor")
      (fields (field (name "PUBLISHER") "Altium Limited"))
      (libsource (lib "Miscellaneous Devices") (part "Res Semi"))
    )
    (comp (ref "R43")
      (value "1K")
      (footprint "C0805")
      (description "Semiconductor Resistor")
      (fields (field (name "PUBLISHER") "Altium Limited"))
      (libsource (lib "Miscellaneous Devices") (part "Res Semi"))
    )
    (comp (ref "R44")
      (value "RPot")
      (footprint "Multi-Turn")
      (description "Potentiometer")
      (fields (field (name "ALTIUM_VALUE") "1K") (field (name "PUBLISHER") "Altium Limited"))
      (libsource (lib "Miscellaneous Devices") (part "RPot"))
    )
    (comp (ref "S1")
      (value "SW DIP-4")
      (footprint "DIP Switch x4:dip switch x4")
      (description "DIP Switch, 4 Position, SPST")
      (fields (field (name "PUBLISHER") "Altium Limited"))
      (libsource (lib "Miscellaneous Devices") (part "SW DIP-4"))
    )
    (comp (ref "SW1") (value "?") (footprint "Sw_Tact 2PIN") (libsource (lib "My_LIB") (part "Micro Switch")))
    (comp (ref "SW2") (value "?") (footprint "Sw_Tact 2PIN") (libsource (lib "My_LIB") (part "Micro Switch")))
    (comp (ref "SW3") (value "?") (footprint "Sw_Tact 2PIN") (libsource (lib "My_LIB") (part "Micro Switch")))
    (comp (ref "SW4") (value "?") (footprint "Sw_Tact 2PIN") (libsource (lib "My_LIB") (part "Micro Switch")))
    (comp (ref "SW5") (value "?") (footprint "Sw_Tact 2PIN") (libsource (lib "My_LIB") (part "Micro Switch")))
    (comp (ref "SW6") (value "?") (footprint "Sw_Tact 2PIN") (libsource (lib "My_LIB") (part "Micro Switch")))
    (comp (ref "SW7")
      (value "SW-SPST")
      (footprint "DSW 1")
      (description "Single-Pole, Single-Throw Switch")
      (fields (field (name "PUBLISHER") "Altium Limited"))
      (libsource (lib "Miscellaneous Devices") (part "SW-SPST"))
    )
    (comp (ref "U1")
      (value "AMS1117")
      (footprint "Miscellaneous Devices:SOT223_L")
      (libsource (lib "AMS1117") (part "AMS1117"))
    )
    (comp (ref "U2")
      (value "PL-2303")
      (footprint "SOP65P780X200-28N")
      (description "USB to Serial Bridge Controller")
      (fields (field (name "MF") "Prolific Technology"))
      (libsource (lib "PL-2303") (part "PL-2303"))
    )
    (comp (ref "U3")
      (value "STM32F103RET6")
      (footprint "LQFP64")
      (libsource (lib "STMicroelectronics STM32 F1") (part "STM32F103RET6"))
    )
    (comp (ref "U4") (value "LM35") (footprint "TO-92") (libsource (lib "My_LIB") (part "LM35")))
    (comp (ref "U5")
      (value "MQ-2")
      (footprint "SNR6-D19.0MM")
      (description "D-Sub MIL Spec Connectors Microminiature Series .050")
      (fields (field (name "MF") "AirBorn"))
      (libsource (lib "DIP-GAS-MQ-2_6P-D19MM_") (part "DIP-GAS-MQ-2(6P-D19MM)"))
    )
    (comp (ref "U6")
      (value "TEM-HUM-DHT11(4P-15.5X12.0MM)")
      (footprint "SNR4-2.54-15.5X12.0X5.5MM")
      (description "Servo AC 100 ~ 120VAC Supply 10A 120V Load")
      (fields (field (name "MP") "DHT11") (field (name "MF") "Panasonic Industrial Automation Sales"))
      (libsource (lib "TEM-HUM-DHT11_4P-15.5X12.0MM_") (part "TEM-HUM-DHT11(4P-15.5X12.0MM)"))
    )
    (comp (ref "Y1")
      (value "12MHz")
      (footprint "Xtal")
      (description "Crystal Oscillator")
      (fields (field (name "PUBLISHER") "Altium Limited"))
      (libsource (lib "Miscellaneous Devices") (part "XTAL"))
    )
    (comp (ref "Y2")
      (value "8 MHz")
      (footprint "Xtal")
      (description "12 MHz")
      (fields (field (name "PUBLISHER") "Altium Limited"))
      (libsource (lib "Miscellaneous Devices") (part "XTAL"))
    )
    (comp (ref "Y3")
      (value "8 MHz")
      (footprint "Xtal")
      (description "12 MHz")
      (fields (field (name "PUBLISHER") "Altium Limited"))
      (libsource (lib "Miscellaneous Devices") (part "XTAL"))
    )
  )
  (nets
    (net (code "1") (name "/5V0U") (class "Default")
      (node (ref "C12") (pin "2") (pinfunction "2_2") (pintype "passive"))
      (node (ref "C13") (pin "2") (pinfunction "2_2") (pintype "passive"))
      (node (ref "C14") (pin "2") (pinfunction "2_2") (pintype "passive"))
      (node (ref "D4") (pin "1") (pinfunction "A_1") (pintype "passive"))
      (node (ref "L4") (pin "1") (pinfunction "1_1") (pintype "passive"))
      (node (ref "U2") (pin "20") (pinfunction "VDD_20") (pintype "power_in"))
      (node (ref "U2") (pin "8") (pinfunction "VDD_8") (pintype "power_in"))
    )
    (net (code "2") (name "/5V0USB") (class "Default")
      (node (ref "C11") (pin "2") (pinfunction "2_2") (pintype "passive"))
      (node (ref "C8") (pin "2") (pinfunction "2_2") (pintype "passive"))
      (node (ref "D3") (pin "1") (pinfunction "A_1") (pintype "passive"))
      (node (ref "L2") (pin "1") (pinfunction "1_1") (pintype "passive"))
    )
    (net (code "3") (name "/Alarm on {slash} off") (class "Default")
      (node (ref "R28") (pin "2") (pinfunction "2_2") (pintype "passive"))
      (node (ref "S1") (pin "2") (pinfunction "A2_2") (pintype "passive"))
      (node (ref "U3") (pin "59") (pinfunction "PB7_59") (pintype "bidirectional"))
    )
    (net (code "4") (name "/Auto") (class "Default")
      (node (ref "R16") (pin "1") (pinfunction "1_1") (pintype "passive"))
      (node (ref "U3") (pin "57") (pinfunction "PB5_57") (pintype "bidirectional"))
    )
    (net (code "5") (name "/Auto {slash} Manual") (class "Default")
      (node (ref "R27") (pin "2") (pinfunction "2_2") (pintype "passive"))
      (node (ref "S1") (pin "1") (pinfunction "A1_1") (pintype "passive"))
      (node (ref "U3") (pin "26") (pinfunction "PB0_26") (pintype "bidirectional"))
    )
    (net (code "6") (name "/BOOT0") (class "Default")
      (node (ref "P3") (pin "1") (pinfunction "1_1") (pintype "passive"))
      (node (ref "R40") (pin "1") (pinfunction "1_1") (pintype "passive"))
      (node (ref "U3") (pin "60") (pinfunction "BOOT0_60") (pintype "input"))
    )
    (net (code "7") (name "/CLOCK") (class "Default")
      (node (ref "R26") (pin "1") (pinfunction "1_1") (pintype "passive"))
      (node (ref "U3") (pin "53") (pinfunction "PC12_53") (pintype "bidirectional"))
    )
    (net (code "8") (name "/CMD") (class "Default")
      (node (ref "R21") (pin "2") (pinfunction "2_2") (pintype "passive"))
      (node (ref "R31") (pin "1") (pinfunction "1_1") (pintype "passive"))
      (node (ref "U3") (pin "54") (pinfunction "PD2_54") (pintype "bidirectional"))
    )
    (net (code "9") (name "/Cooler") (class "Default")
      (node (ref "R29") (pin "2") (pinfunction "2_2") (pintype "passive"))
      (node (ref "S1") (pin "3") (pinfunction "A3_3") (pintype "passive"))
      (node (ref "U3") (pin "23") (pinfunction "PA7_23") (pintype "bidirectional"))
    )
    (net (code "10") (name "/Cooler on{slash}off") (class "Default")
      (node (ref "R43") (pin "1") (pinfunction "1_1") (pintype "passive"))
      (node (ref "U3") (pin "20") (pinfunction "PA4_20") (pintype "bidirectional"))
    )
    (net (code "11") (name "/D4") (class "Default")
      (node (ref "LCD1") (pin "11") (pinfunction "D4_11") (pintype "passive"))
      (node (ref "U3") (pin "61") (pinfunction "PB8_61") (pintype "bidirectional"))
    )
    (net (code "12") (name "/D5") (class "Default")
      (node (ref "LCD1") (pin "12") (pinfunction "D5_12") (pintype "passive"))
      (node (ref "U3") (pin "62") (pinfunction "PB9_62") (pintype "bidirectional"))
    )
    (net (code "13") (name "/D6") (class "Default")
      (node (ref "LCD1") (pin "13") (pinfunction "D6_13") (pintype "passive"))
      (node (ref "U3") (pin "29") (pinfunction "PB10_29") (pintype "bidirectional"))
    )
    (net (code "14") (name "/D7") (class "Default")
      (node (ref "LCD1") (pin "14") (pinfunction "D7_14") (pintype "passive"))
      (node (ref "U3") (pin "30") (pinfunction "PB11_30") (pintype "bidirectional"))
    )
    (net (code "15") (name "/DATA_0") (class "Default")
      (node (ref "R22") (pin "2") (pinfunction "2_2") (pintype "passive"))
      (node (ref "R25") (pin "1") (pinfunction "1_1") (pintype "passive"))
      (node (ref "U3") (pin "39") (pinfunction "PC8_39") (pintype "bidirectional"))
    )
    (net (code "16") (name "/DATA_1") (class "Default")
      (node (ref "R23") (pin "2") (pinfunction "2_2") (pintype "passive"))
      (node (ref "R24") (pin "1") (pinfunction "1_1") (pintype "passive"))
      (node (ref "U3") (pin "40") (pinfunction "PC9_40") (pintype "bidirectional"))
    )
    (net (code "17") (name "/DATA_2") (class "Default")
      (node (ref "R19") (pin "2") (pinfunction "2_2") (pintype "passive"))
      (node (ref "R34") (pin "1") (pinfunction "1_1") (pintype "passive"))
      (node (ref "U3") (pin "51") (pinfunction "PC10_51") (pintype "bidirectional"))
    )
    (net (code "18") (name "/DATA_3") (class "Default")
      (node (ref "R20") (pin "2") (pinfunction "2_2") (pintype "passive"))
      (node (ref "R33") (pin "1") (pinfunction "1_1") (pintype "passive"))
      (node (ref "U3") (pin "52") (pinfunction "PC11_52") (pintype "bidirectional"))
    )
    (net (code "19") (name "/DM") (class "Default")
      (node (ref "R5") (pin "2") (pinfunction "2_2") (pintype "passive"))
      (node (ref "U2") (pin "16") (pinfunction "DM_16") (pintype "bidirectional"))
    )
    (net (code "20") (name "/DM_USB") (class "Default")
      (node (ref "R4") (pin "2") (pinfunction "2_2") (pintype "passive"))
      (node (ref "U3") (pin "44") (pinfunction "PA11_44") (pintype "bidirectional"))
    )
    (net (code "21") (name "/DP") (class "Default")
      (node (ref "R9") (pin "2") (pinfunction "2_2") (pintype "passive"))
      (node (ref "U2") (pin "15") (pinfunction "DP_15") (pintype "bidirectional"))
    )
    (net (code "22") (name "/DP_USB") (class "Default")
      (node (ref "R6") (pin "2") (pinfunction "2_2") (pintype "passive"))
      (node (ref "U3") (pin "45") (pinfunction "PA12_45") (pintype "bidirectional"))
    )
    (net (code "23") (name "/Direction") (class "Default")
      (node (ref "R37") (pin "1") (pinfunction "1_1") (pintype "passive"))
      (node (ref "SW4") (pin "1") (pinfunction "1_1") (pintype "passive"))
      (node (ref "U3") (pin "55") (pinfunction "PB3_55") (pintype "bidirectional"))
    )
    (net (code "24") (name "/EN") (class "Default")
      (node (ref "LCD1") (pin "6") (pinfunction "E_6") (pintype "passive"))
      (node (ref "U3") (pin "10") (pinfunction "PC2_10") (pintype "bidirectional"))
    )
    (net (code "25") (name "/Gas") (class "Default")
      (node (ref "R15") (pin "2") (pinfunction "TAP_2") (pintype "passive"))
      (node (ref "U3") (pin "16") (pinfunction "PA2_16") (pintype "bidirectional"))
      (node (ref "U5") (pin "2") (pinfunction "B0_2") (pintype "bidirectional"))
      (node (ref "U5") (pin "4") (pinfunction "B1_4") (pintype "bidirectional"))
    )
    (net (code "26") (name "/Gas on{slash}off") (class "Default")
      (node (ref "R42") (pin "1") (pinfunction "1_1") (pintype "passive"))
      (node (ref "U3") (pin "22") (pinfunction "PA6_22") (pintype "bidirectional"))
    )
    (net (code "27") (name "/Heater") (class "Default")
      (node (ref "R30") (pin "2") (pinfunction "2_2") (pintype "passive"))
      (node (ref "S1") (pin "4") (pinfunction "A4_4") (pintype "passive"))
      (node (ref "U3") (pin "41") (pinfunction "PA8_41") (pintype "bidirectional"))
    )
    (net (code "28") (name "/Heater on{slash}off") (class "Default")
      (node (ref "R41") (pin "1") (pinfunction "1_1") (pintype "passive"))
      (node (ref "U3") (pin "21") (pinfunction "PA5_21") (pintype "bidirectional"))
    )
    (net (code "29") (name "/Manual") (class "Default")
      (node (ref "R17") (pin "1") (pinfunction "1_1") (pintype "passive"))
      (node (ref "U3") (pin "58") (pinfunction "PB6_58") (pintype "bidirectional"))
    )
    (net (code "30") (name "/OSC_CLOCK_IN") (class "Default")
      (node (ref "C16") (pin "2") (pinfunction "2_2") (pintype "passive"))
      (node (ref "U3") (pin "3") (pinfunction "PC14-OSC32_IN_3") (pintype "bidirectional"))
      (node (ref "Y3") (pin "2") (pinfunction "OSC2_2") (pintype "passive"))
    )
    (net (code "31") (name "/OSC_CLOCK_OUT") (class "Default")
      (node (ref "C19") (pin "2") (pinfunction "2_2") (pintype "passive"))
      (node (ref "U3") (pin "4") (pinfunction "PC15-OSC32_OUT_4") (pintype "bidirectional"))
      (node (ref "Y3") (pin "1") (pinfunction "OSC1_1") (pintype "passive"))
    )
    (net (code "32") (name "/OSC_IN") (class "Default")
      (node (ref "C15") (pin "2") (pinfunction "2_2") (pintype "passive"))
      (node (ref "U3") (pin "5") (pinfunction "PD0-OSC_IN_5") (pintype "bidirectional"))
      (node (ref "Y2") (pin "2") (pinfunction "OSC2_2") (pintype "passive"))
    )
    (net (code "33") (name "/OSC_OUT") (class "Default")
      (node (ref "C17") (pin "2") (pinfunction "2_2") (pintype "passive"))
      (node (ref "U3") (pin "6") (pinfunction "PD1_6") (pintype "bidirectional"))
      (node (ref "Y2") (pin "1") (pinfunction "OSC1_1") (pintype "passive"))
    )
    (net (code "34") (name "/PWM_Alarm") (class "Default")
      (node (ref "R8") (pin "2") (pinfunction "2_2") (pintype "passive"))
      (node (ref "U3") (pin "50") (pinfunction "PA15_50") (pintype "bidirectional"))
    )
    (net (code "35") (name "/PWM_Gas") (class "Default")
      (node (ref "R7") (pin "2") (pinfunction "2_2") (pintype "passive"))
      (node (ref "U3") (pin "17") (pinfunction "PA3_17") (pintype "bidirectional"))
    )
    (net (code "36") (name "/RESET") (class "Default")
      (node (ref "C18") (pin "2") (pinfunction "2_2") (pintype "passive"))
      (node (ref "R11") (pin "1") (pinfunction "1_1") (pintype "passive"))
      (node (ref "SW1") (pin "2") (pinfunction "2_2") (pintype "passive"))
      (node (ref "U3") (pin "7") (pinfunction "NRST_7") (pintype "bidirectional"))
    )
    (net (code "37") (name "/RS") (class "Default")
      (node (ref "LCD1") (pin "4") (pinfunction "RS_4") (pintype "passive"))
      (node (ref "U3") (pin "8") (pinfunction "PC0_8") (pintype "bidirectional"))
    )
    (net (code "38") (name "/RW") (class "Default")
      (node (ref "LCD1") (pin "5") (pinfunction "R~{W}_5") (pintype "passive"))
      (node (ref "U3") (pin "9") (pinfunction "PC1_9") (pintype "bidirectional"))
    )
    (net (code "39") (name "/RXD_STM32") (class "Default")
      (node (ref "U2") (pin "1") (pinfunction "TXD_1") (pintype "output"))
      (node (ref "U3") (pin "43") (pinfunction "PA10_43") (pintype "bidirectional"))
    )
    (net (code "40") (name "/Reset Clock {slash} Date {slash} Alarm") (class "Default")
      (node (ref "R39") (pin "1") (pinfunction "1_1") (pintype "passive"))
      (node (ref "SW6") (pin "1") (pinfunction "1_1") (pintype "passive"))
      (node (ref "U3") (pin "56") (pinfunction "PB4_56") (pintype "bidirectional"))
    )
    (net (code "41") (name "/SWCLK") (class "Default")
      (node (ref "P2") (pin "3") (pinfunction "3_3") (pintype "passive"))
      (node (ref "U3") (pin "49") (pinfunction "PA14_49") (pintype "bidirectional"))
    )
    (net (code "42") (name "/SWDIO") (class "Default")
      (node (ref "P2") (pin "2") (pinfunction "2_2") (pintype "passive"))
      (node (ref "U3") (pin "46") (pinfunction "PA13_46") (pintype "bidirectional"))
    )
    (net (code "43") (name "/Set Clock {slash} Date {slash} Alarm") (class "Default")
      (node (ref "R36") (pin "1") (pinfunction "1_1") (pintype "passive"))
      (node (ref "SW3") (pin "1") (pinfunction "1_1") (pintype "passive"))
      (node (ref "U3") (pin "28") (pinfunction "PB2_28") (pintype "bidirectional"))
    )
    (net (code "44") (name "/Start Clock {slash} Date {slash} Alarm") (class "Default")
      (node (ref "R38") (pin "1") (pinfunction "1_1") (pintype "passive"))
      (node (ref "SW5") (pin "1") (pinfunction "1_1") (pintype "passive"))
    )
    (net (code "45") (name "/Start Setting Clock {slash} Date {slash} Alarm") (class "Default")
      (node (ref "R35") (pin "1") (pinfunction "1_1") (pintype "passive"))
      (node (ref "SW2") (pin "1") (pinfunction "1_1") (pintype "passive"))
      (node (ref "U3") (pin "27") (pinfunction "PB1_27") (pintype "bidirectional"))
    )
    (net (code "46") (name "/TXD_STM32") (class "Default")
      (node (ref "U2") (pin "5") (pinfunction "RXD_5") (pintype "input"))
      (node (ref "U3") (pin "42") (pinfunction "PA9_42") (pintype "bidirectional"))
    )
    (net (code "47") (name "/Temp {slash} Hum_Digital") (class "Default")
      (node (ref "R32") (pin "1") (pinfunction "1_1") (pintype "passive"))
      (node (ref "U3") (pin "15") (pinfunction "PA1_15") (pintype "bidirectional"))
      (node (ref "U6") (pin "2") (pinfunction "DATA_2") (pintype "bidirectional"))
    )
    (net (code "48") (name "/Temp_Analog") (class "Default")
      (node (ref "U3") (pin "14") (pinfunction "PA0-WKUP_14") (pintype "bidirectional"))
      (node (ref "U4") (pin "2") (pinfunction "VOUT_2") (pintype "passive"))
    )
    (net (code "49") (name "3V3") (class "Default")
      (node (ref "C2") (pin "2") (pinfunction "2_2") (pintype "passive"))
      (node (ref "C22") (pin "2") (pinfunction "2_2") (pintype "passive"))
      (node (ref "C23") (pin "2") (pinfunction "2_2") (pintype "passive"))
      (node (ref "C24") (pin "2") (pinfunction "2_2") (pintype "passive"))
      (node (ref "C25") (pin "2") (pinfunction "2_2") (pintype "passive"))
      (node (ref "C26") (pin "2") (pinfunction "2_2") (pintype "passive"))
      (node (ref "C28") (pin "2") (pinfunction "2_2") (pintype "passive"))
      (node (ref "C4") (pin "2") (pinfunction "2_2") (pintype "passive"))
      (node (ref "J3") (pin "4") (pinfunction "VCC_4") (pintype "passive"))
      (node (ref "L1") (pin "1") (pinfunction "1_1") (pintype "passive"))
      (node (ref "P2") (pin "1") (pinfunction "1_1") (pintype "passive"))
      (node (ref "P3") (pin "2") (pinfunction "2_2") (pintype "passive"))
      (node (ref "R1") (pin "2") (pinfunction "2_2") (pintype "passive"))
      (node (ref "R10") (pin "2") (pinfunction "2_2") (pintype "passive"))
      (node (ref "R11") (pin "2") (pinfunction "2_2") (pintype "passive"))
      (node (ref "R19") (pin "1") (pinfunction "1_1") (pintype "passive"))
      (node (ref "R20") (pin "1") (pinfunction "1_1") (pintype "passive"))
      (node (ref "R21") (pin "1") (pinfunction "1_1") (pintype "passive"))
      (node (ref "R22") (pin "1") (pinfunction "1_1") (pintype "passive"))
      (node (ref "R23") (pin "1") (pinfunction "1_1") (pintype "passive"))
      (node (ref "R27") (pin "1") (pinfunction "1_1") (pintype "passive"))
      (node (ref "R28") (pin "1") (pinfunction "1_1") (pintype "passive"))
      (node (ref "R29") (pin "1") (pinfunction "1_1") (pintype "passive"))
      (node (ref "R30") (pin "1") (pinfunction "1_1") (pintype "passive"))
      (node (ref "R32") (pin "2") (pinfunction "2_2") (pintype "passive"))
      (node (ref "R39") (pin "2") (pinfunction "2_2") (pintype "passive"))
      (node (ref "SW2") (pin "2") (pinfunction "2_2") (pintype "passive"))
      (node (ref "SW3") (pin "2") (pinfunction "2_2") (pintype "passive"))
      (node (ref "SW4") (pin "2") (pinfunction "2_2") (pintype "passive"))
      (node (ref "SW5") (pin "2") (pinfunction "2_2") (pintype "passive"))
      (node (ref "U1") (pin "2") (pinfunction "VOUT_2") (pintype "passive"))
      (node (ref "U1") (pin "4") (pinfunction "VOUT_4") (pintype "passive"))
      (node (ref "U3") (pin "19") (pinfunction "VDD_4_19") (pintype "power_in"))
      (node (ref "U3") (pin "32") (pinfunction "VDD_1_32") (pintype "power_in"))
      (node (ref "U3") (pin "48") (pinfunction "VDD_2_48") (pintype "power_in"))
      (node (ref "U3") (pin "64") (pinfunction "VDD_3_64") (pintype "power_in"))
      (node (ref "U6") (pin "1") (pinfunction "VDD_1") (pintype "power_in"))
    )
    (net (code "50") (name "3V3U") (class "Default")
      (node (ref "C10") (pin "2") (pinfunction "2_2") (pintype "passive"))
      (node (ref "C7") (pin "2") (pinfunction "2_2") (pintype "passive"))
      (node (ref "C9") (pin "2") (pinfunction "2_2") (pintype "passive"))
      (node (ref "R12") (pin "2") (pinfunction "2_2") (pintype "passive"))
      (node (ref "R3") (pin "1") (pinfunction "1_1") (pintype "passive"))
      (node (ref "U2") (pin "17") (pinfunction "VDD_3V3_17") (pintype "power_in"))
      (node (ref "U2") (pin "4") (pinfunction "VDD_232_4") (pintype "power_in"))
    )
    (net (code "51") (name "3V3_A") (class "Default")
      (node (ref "C5") (pin "2") (pinfunction "2_2") (pintype "passive"))
      (node (ref "L1") (pin "2") (pinfunction "2_2") (pintype "passive"))
      (node (ref "U3") (pin "13") (pinfunction "VDDA_13") (pintype "power_in"))
    )
    (net (code "52") (name "5V0") (class "Default")
      (node (ref "C1") (pin "2") (pinfunction "2_2") (pintype "passive"))
      (node (ref "C3") (pin "2") (pinfunction "2_2") (pintype "passive"))
      (node (ref "D3") (pin "2") (pinfunction "K_2") (pintype "passive"))
      (node (ref "D4") (pin "2") (pinfunction "K_2") (pintype "passive"))
      (node (ref "D7") (pin "C") (pinfunction "C_C") (pintype "passive"))
      (node (ref "D8") (pin "C") (pinfunction "C_C") (pintype "passive"))
      (node (ref "D9") (pin "C") (pinfunction "C_C") (pintype "passive"))
      (node (ref "K1") (pin "4") (pinfunction "T1_4") (pintype "passive"))
      (node (ref "K2") (pin "4") (pinfunction "T1_4") (pintype "passive"))
      (node (ref "K3") (pin "4") (pinfunction "T1_4") (pintype "passive"))
      (node (ref "LCD1") (pin "15") (pinfunction "A_15") (pintype "passive"))
      (node (ref "LCD1") (pin "2") (pinfunction "VCC_2") (pintype "passive"))
      (node (ref "LS1") (pin "P") (pinfunction "POS_P") (pintype "passive"))
      (node (ref "LS2") (pin "P") (pinfunction "POS_P") (pintype "passive"))
      (node (ref "R13") (pin "1") (pinfunction "1_1") (pintype "passive"))
      (node (ref "R14") (pin "1") (pinfunction "1_1") (pintype "passive"))
      (node (ref "R15") (pin "1") (pinfunction "TOP_1") (pintype "passive"))
      (node (ref "R2") (pin "1") (pinfunction "1_1") (pintype "passive"))
      (node (ref "R44") (pin "1") (pinfunction "TOP_1") (pintype "passive"))
      (node (ref "SW7") (pin "1") (pinfunction "COMMON_1") (pintype "passive"))
      (node (ref "U1") (pin "3") (pinfunction "VIN_3") (pintype "passive"))
      (node (ref "U4") (pin "1") (pinfunction "+VS_1") (pintype "passive"))
      (node (ref "U5") (pin "1") (pinfunction "A0_1") (pintype "bidirectional"))
      (node (ref "U5") (pin "3") (pinfunction "A1_3") (pintype "bidirectional"))
      (node (ref "U5") (pin "5") (pinfunction "H@1_5") (pintype "bidirectional"))
    )
    (net (code "53") (name "DC_IN") (class "Default")
      (node (ref "J4") (pin "4") (pinfunction "2_4") (pintype "passive"))
      (node (ref "SW7") (pin "2") (pinfunction "NO_2") (pintype "passive"))
    )
    (net (code "54") (name "GND") (class "Default")
      (node (ref "BT1") (pin "2") (pinfunction "-_2") (pintype "passive"))
      (node (ref "C1") (pin "1") (pinfunction "1_1") (pintype "passive"))
      (node (ref "C10") (pin "1") (pinfunction "1_1") (pintype "passive"))
      (node (ref "C11") (pin "1") (pinfunction "1_1") (pintype "passive"))
      (node (ref "C12") (pin "1") (pinfunction "1_1") (pintype "passive"))
      (node (ref "C13") (pin "1") (pinfunction "1_1") (pintype "passive"))
      (node (ref "C14") (pin "1") (pinfunction "1_1") (pintype "passive"))
      (node (ref "C15") (pin "1") (pinfunction "1_1") (pintype "passive"))
      (node (ref "C16") (pin "1") (pinfunction "1_1") (pintype "passive"))
      (node (ref "C17") (pin "1") (pinfunction "1_1") (pintype "passive"))
      (node (ref "C18") (pin "1") (pinfunction "1_1") (pintype "passive"))
      (node (ref "C19") (pin "1") (pinfunction "1_1") (pintype "passive"))
      (node (ref "C2") (pin "1") (pinfunction "1_1") (pintype "passive"))
      (node (ref "C20") (pin "1") (pinfunction "1_1") (pintype "passive"))
      (node (ref "C21") (pin "1") (pinfunction "1_1") (pintype "passive"))
      (node (ref "C22") (pin "1") (pinfunction "1_1") (pintype "passive"))
      (node (ref "C23") (pin "1") (pinfunction "1_1") (pintype "passive"))
      (node (ref "C24") (pin "1") (pinfunction "1_1") (pintype "passive"))
      (node (ref "C25") (pin "1") (pinfunction "1_1") (pintype "passive"))
      (node (ref "C26") (pin "1") (pinfunction "1_1") (pintype "passive"))
      (node (ref "C27") (pin "1") (pinfunction "1_1") (pintype "passive"))
      (node (ref "C28") (pin "1") (pinfunction "1_1") (pintype "passive"))
      (node (ref "C3") (pin "1") (pinfunction "1_1") (pintype "passive"))
      (node (ref "C4") (pin "1") (pinfunction "1_1") (pintype "passive"))
      (node (ref "C6") (pin "1") (pinfunction "1_1") (pintype "passive"))
      (node (ref "C7") (pin "1") (pinfunction "1_1") (pintype "passive"))
      (node (ref "C8") (pin "1") (pinfunction "1_1") (pintype "passive"))
      (node (ref "C9") (pin "1") (pinfunction "1_1") (pintype "passive"))
      (node (ref "D1") (pin "2") (pinfunction "K_2") (pintype "passive"))
      (node (ref "J1") (pin "4") (pinfunction "GND_4") (pintype "power_in"))
      (node (ref "J2") (pin "4") (pinfunction "GND_4") (pintype "power_in"))
      (node (ref "J3") (pin "6") (pinfunction "GND_6") (pintype "passive"))
      (node (ref "J3") (pin "SH1") (pinfunction "GND1_SH1") (pintype "passive"))
      (node (ref "J3") (pin "SH2") (pinfunction "GND2_SH2") (pintype "passive"))
      (node (ref "J3") (pin "SH3") (pinfunction "GND3_SH3") (pintype "passive"))
      (node (ref "J3") (pin "SH4") (pinfunction "GND4_SH4") (pintype "passive"))
      (node (ref "J4") (pin "2") (pinfunction "4_2") (pintype "passive"))
      (node (ref "J4") (pin "3") (pinfunction "5_3") (pintype "passive"))
      (node (ref "L10") (pin "1") (pinfunction "1_1") (pintype "passive"))
      (node (ref "L3") (pin "1") (pinfunction "1_1") (pintype "passive"))
      (node (ref "L9") (pin "1") (pinfunction "1_1") (pintype "passive"))
      (node (ref "LCD1") (pin "1") (pinfunction "GND_1") (pintype "passive"))
      (node (ref "LCD1") (pin "16") (pinfunction "K_16") (pintype "passive"))
      (node (ref "P2") (pin "4") (pinfunction "4_4") (pintype "passive"))
      (node (ref "Q1") (pin "1") (pinfunction "E_1") (pintype "passive"))
      (node (ref "Q2") (pin "1") (pinfunction "E_1") (pintype "passive"))
      (node (ref "Q3") (pin "1") (pinfunction "E_1") (pintype "passive"))
      (node (ref "Q4") (pin "1") (pinfunction "E_1") (pintype "passive"))
      (node (ref "Q5") (pin "2") (pinfunction "E_2") (pintype "passive"))
      (node (ref "Q6") (pin "2") (pinfunction "E_2") (pintype "passive"))
      (node (ref "Q7") (pin "2") (pinfunction "E_2") (pintype "passive"))
      (node (ref "R15") (pin "3") (pinfunction "BOT_3") (pintype "passive"))
      (node (ref "R18") (pin "1") (pinfunction "1_1") (pintype "passive"))
      (node (ref "R35") (pin "2") (pinfunction "2_2") (pintype "passive"))
      (node (ref "R36") (pin "2") (pinfunction "2_2") (pintype "passive"))
      (node (ref "R37") (pin "2") (pinfunction "2_2") (pintype "passive"))
      (node (ref "R38") (pin "2") (pinfunction "2_2") (pintype "passive"))
      (node (ref "R40") (pin "2") (pinfunction "2_2") (pintype "passive"))
      (node (ref "R44") (pin "2") (pinfunction "BOT_2") (pintype "passive"))
      (node (ref "S1") (pin "5") (pinfunction "B4_5") (pintype "passive"))
      (node (ref "S1") (pin "6") (pinfunction "B3_6") (pintype "passive"))
      (node (ref "S1") (pin "7") (pinfunction "B2_7") (pintype "passive"))
      (node (ref "S1") (pin "8") (pinfunction "B1_8") (pintype "passive"))
      (node (ref "SW1") (pin "1") (pinfunction "1_1") (pintype "passive"))
      (node (ref "SW6") (pin "2") (pinfunction "2_2") (pintype "passive"))
      (node (ref "U1") (pin "1") (pinfunction "ADJ/GND_1") (pintype "passive"))
      (node (ref "U2") (pin "18") (pinfunction "GND_3V3_18") (pintype "power_in"))
      (node (ref "U2") (pin "21") (pinfunction "GND_21") (pintype "power_in"))
      (node (ref "U2") (pin "25") (pinfunction "GND_PLL_25") (pintype "power_in"))
      (node (ref "U2") (pin "26") (pinfunction "PLL_TEST_26") (pintype "input"))
      (node (ref "U2") (pin "7") (pinfunction "GND_7") (pintype "power_in"))
      (node (ref "U3") (pin "18") (pinfunction "VSS_4_18") (pintype "power_in"))
      (node (ref "U3") (pin "31") (pinfunction "VSS_1_31") (pintype "power_in"))
      (node (ref "U3") (pin "47") (pinfunction "VSS_2_47") (pintype "power_in"))
      (node (ref "U3") (pin "63") (pinfunction "VSS_3_63") (pintype "power_in"))
      (node (ref "U4") (pin "3") (pinfunction "-VS_3") (pintype "passive"))
      (node (ref "U6") (pin "4") (pinfunction "GND_4") (pintype "power_in"))
    )
    (net (code "55") (name "GND_A") (class "Default")
      (node (ref "C5") (pin "1") (pinfunction "1_1") (pintype "passive"))
      (node (ref "L3") (pin "2") (pinfunction "2_2") (pintype "passive"))
      (node (ref "U3") (pin "12") (pinfunction "VSSA_12") (pintype "power_in"))
    )
    (net (code "56") (name "Net-(D1-A)") (class "Default")
      (node (ref "D1") (pin "1") (pinfunction "A_1") (pintype "passive"))
      (node (ref "R1") (pin "1") (pinfunction "1_1") (pintype "passive"))
    )
    (net (code "57") (name "Net-(D2-A)") (class "Default")
      (node (ref "D2") (pin "1") (pinfunction "A_1") (pintype "passive"))
      (node (ref "R2") (pin "2") (pinfunction "2_2") (pintype "passive"))
    )
    (net (code "58") (name "Net-(D2-K)") (class "Default")
      (node (ref "D2") (pin "2") (pinfunction "K_2") (pintype "passive"))
      (node (ref "LS1") (pin "N") (pinfunction "NEG_N") (pintype "passive"))
      (node (ref "Q1") (pin "3") (pinfunction "C_3") (pintype "passive"))
    )
    (net (code "59") (name "Net-(D5-A)") (class "Default")
      (node (ref "D5") (pin "1") (pinfunction "A_1") (pintype "passive"))
      (node (ref "R13") (pin "2") (pinfunction "2_2") (pintype "passive"))
    )
    (net (code "60") (name "Net-(D5-K)") (class "Default")
      (node (ref "D5") (pin "2") (pinfunction "K_2") (pintype "passive"))
      (node (ref "Q3") (pin "3") (pinfunction "C_3") (pintype "passive"))
    )
    (net (code "61") (name "Net-(D6-A)") (class "Default")
      (node (ref "D6") (pin "1") (pinfunction "A_1") (pintype "passive"))
      (node (ref "R14") (pin "2") (pinfunction "2_2") (pintype "passive"))
    )
    (net (code "62") (name "Net-(D6-K)") (class "Default")
      (node (ref "D6") (pin "2") (pinfunction "K_2") (pintype "passive"))
      (node (ref "Q4") (pin "3") (pinfunction "C_3") (pintype "passive"))
    )
    (net (code "63") (name "Net-(J1-D+)") (class "Default")
      (node (ref "J1") (pin "3") (pinfunction "D+_3") (pintype "input"))
      (node (ref "L7") (pin "2") (pinfunction "2_2") (pintype "passive"))
    )
    (net (code "64") (name "Net-(J1-D-)") (class "Default")
      (node (ref "J1") (pin "2") (pinfunction "D-_2") (pintype "input"))
      (node (ref "L5") (pin "2") (pinfunction "2_2") (pintype "passive"))
    )
    (net (code "65") (name "Net-(J1-SHLD)") (class "Default")
      (node (ref "J1") (pin "5") (pinfunction "SHLD_5") (pintype "passive"))
      (node (ref "L9") (pin "2") (pinfunction "2_2") (pintype "passive"))
    )
    (net (code "66") (name "Net-(J1-VBUS)") (class "Default")
      (node (ref "J1") (pin "1") (pinfunction "VBUS_1") (pintype "power_in"))
      (node (ref "L2") (pin "2") (pinfunction "2_2") (pintype "passive"))
    )
    (net (code "67") (name "Net-(J2-D+)") (class "Default")
      (node (ref "J2") (pin "3") (pinfunction "D+_3") (pintype "input"))
      (node (ref "L8") (pin "2") (pinfunction "2_2") (pintype "passive"))
    )
    (net (code "68") (name "Net-(J2-D-)") (class "Default")
      (node (ref "J2") (pin "2") (pinfunction "D-_2") (pintype "input"))
      (node (ref "L6") (pin "2") (pinfunction "2_2") (pintype "passive"))
    )
    (net (code "69") (name "Net-(J2-SHLD)") (class "Default")
      (node (ref "J2") (pin "5") (pinfunction "SHLD_5") (pintype "passive"))
      (node (ref "L10") (pin "2") (pinfunction "2_2") (pintype "passive"))
    )
    (net (code "70") (name "Net-(J2-VBUS)") (class "Default")
      (node (ref "J2") (pin "1") (pinfunction "VBUS_1") (pintype "power_in"))
      (node (ref "L4") (pin "2") (pinfunction "2_2") (pintype "passive"))
    )
    (net (code "71") (name "Net-(J3-CMD{slash}DI)") (class "Default")
      (node (ref "J3") (pin "3") (pinfunction "CMD/DI_3") (pintype "passive"))
      (node (ref "R31") (pin "2") (pinfunction "2_2") (pintype "passive"))
    )
    (net (code "72") (name "Net-(J3-DAT0{slash}DO)") (class "Default")
      (node (ref "J3") (pin "7") (pinfunction "DAT0/DO_7") (pintype "passive"))
      (node (ref "R25") (pin "2") (pinfunction "2_2") (pintype "passive"))
    )
    (net (code "73") (name "Net-(J3-DAT1)") (class "Default")
      (node (ref "J3") (pin "8") (pinfunction "DAT1_8") (pintype "passive"))
      (node (ref "R24") (pin "2") (pinfunction "2_2") (pintype "passive"))
    )
    (net (code "74") (name "Net-(J3-DAT2)") (class "Default")
      (node (ref "J3") (pin "1") (pinfunction "DAT2_1") (pintype "passive"))
      (node (ref "R34") (pin "2") (pinfunction "2_2") (pintype "passive"))
    )
    (net (code "75") (name "Net-(J3-DAT3{slash}CS)") (class "Default")
      (node (ref "J3") (pin "2") (pinfunction "DAT3/CS_2") (pintype "passive"))
      (node (ref "R33") (pin "2") (pinfunction "2_2") (pintype "passive"))
    )
    (net (code "76") (name "Net-(J3-SCLK)") (class "Default")
      (node (ref "J3") (pin "5") (pinfunction "SCLK_5") (pintype "passive"))
      (node (ref "R26") (pin "2") (pinfunction "2_2") (pintype "passive"))
    )
    (net (code "77") (name "Net-(K1-COM)") (class "Default")
      (node (ref "K1") (pin "1") (pinfunction "COM_1") (pintype "passive"))
      (node (ref "P4") (pin "2") (pinfunction "2_2") (pintype "passive"))
    )
    (net (code "78") (name "Net-(K1-NC)") (class "Default")
      (node (ref "K1") (pin "2") (pinfunction "NC_2") (pintype "passive"))
      (node (ref "P4") (pin "1") (pinfunction "1_1") (pintype "passive"))
    )
    (net (code "79") (name "Net-(K1-NO)") (class "Default")
      (node (ref "K1") (pin "3") (pinfunction "NO_3") (pintype "passive"))
      (node (ref "P4") (pin "3") (pinfunction "3_3") (pintype "passive"))
    )
    (net (code "80") (name "Net-(K1-T2)") (class "Default")
      (node (ref "D7") (pin "A") (pinfunction "A_A") (pintype "passive"))
      (node (ref "K1") (pin "5") (pinfunction "T2_5") (pintype "passive"))
      (node (ref "Q5") (pin "3") (pinfunction "C_3") (pintype "passive"))
    )
    (net (code "81") (name "Net-(K2-COM)") (class "Default")
      (node (ref "K2") (pin "1") (pinfunction "COM_1") (pintype "passive"))
      (node (ref "P5") (pin "2") (pinfunction "2_2") (pintype "passive"))
    )
    (net (code "82") (name "Net-(K2-NC)") (class "Default")
      (node (ref "K2") (pin "2") (pinfunction "NC_2") (pintype "passive"))
      (node (ref "P5") (pin "1") (pinfunction "1_1") (pintype "passive"))
    )
    (net (code "83") (name "Net-(K2-NO)") (class "Default")
      (node (ref "K2") (pin "3") (pinfunction "NO_3") (pintype "passive"))
      (node (ref "P5") (pin "3") (pinfunction "3_3") (pintype "passive"))
    )
    (net (code "84") (name "Net-(K2-T2)") (class "Default")
      (node (ref "D8") (pin "A") (pinfunction "A_A") (pintype "passive"))
      (node (ref "K2") (pin "5") (pinfunction "T2_5") (pintype "passive"))
      (node (ref "Q6") (pin "3") (pinfunction "C_3") (pintype "passive"))
    )
    (net (code "85") (name "Net-(K3-COM)") (class "Default")
      (node (ref "K3") (pin "1") (pinfunction "COM_1") (pintype "passive"))
      (node (ref "P6") (pin "2") (pinfunction "2_2") (pintype "passive"))
    )
    (net (code "86") (name "Net-(K3-NC)") (class "Default")
      (node (ref "K3") (pin "2") (pinfunction "NC_2") (pintype "passive"))
      (node (ref "P6") (pin "1") (pinfunction "1_1") (pintype "passive"))
    )
    (net (code "87") (name "Net-(K3-NO)") (class "Default")
      (node (ref "K3") (pin "3") (pinfunction "NO_3") (pintype "passive"))
      (node (ref "P6") (pin "3") (pinfunction "3_3") (pintype "passive"))
    )
    (net (code "88") (name "Net-(K3-T2)") (class "Default")
      (node (ref "D9") (pin "A") (pinfunction "A_A") (pintype "passive"))
      (node (ref "K3") (pin "5") (pinfunction "T2_5") (pintype "passive"))
      (node (ref "Q7") (pin "3") (pinfunction "C_3") (pintype "passive"))
    )
    (net (code "89") (name "Net-(L5-Pad1)") (class "Default")
      (node (ref "L5") (pin "1") (pinfunction "1_1") (pintype "passive"))
      (node (ref "R4") (pin "1") (pinfunction "1_1") (pintype "passive"))
    )
    (net (code "90") (name "Net-(L6-Pad1)") (class "Default")
      (node (ref "L6") (pin "1") (pinfunction "1_1") (pintype "passive"))
      (node (ref "R5") (pin "1") (pinfunction "1_1") (pintype "passive"))
    )
    (net (code "91") (name "Net-(L7-Pad1)") (class "Default")
      (node (ref "L7") (pin "1") (pinfunction "1_1") (pintype "passive"))
      (node (ref "R10") (pin "1") (pinfunction "1_1") (pintype "passive"))
      (node (ref "R6") (pin "1") (pinfunction "1_1") (pintype "passive"))
    )
    (net (code "92") (name "Net-(L8-Pad1)") (class "Default")
      (node (ref "L8") (pin "1") (pinfunction "1_1") (pintype "passive"))
      (node (ref "R12") (pin "1") (pinfunction "1_1") (pintype "passive"))
      (node (ref "R9") (pin "1") (pinfunction "1_1") (pintype "passive"))
    )
    (net (code "93") (name "Net-(LCD1-VEE)") (class "Default")
      (node (ref "LCD1") (pin "3") (pinfunction "VEE_3") (pintype "passive"))
      (node (ref "R44") (pin "3") (pinfunction "TAP_3") (pintype "passive"))
    )
    (net (code "94") (name "Net-(LS2-NEG)") (class "Default")
      (node (ref "LS2") (pin "N") (pinfunction "NEG_N") (pintype "passive"))
      (node (ref "Q2") (pin "3") (pinfunction "C_3") (pintype "passive"))
    )
    (net (code "95") (name "Net-(Q1-B)") (class "Default")
      (node (ref "Q1") (pin "2") (pinfunction "B_2") (pintype "passive"))
      (node (ref "R7") (pin "1") (pinfunction "1_1") (pintype "passive"))
    )
    (net (code "96") (name "Net-(Q2-B)") (class "Default")
      (node (ref "Q2") (pin "2") (pinfunction "B_2") (pintype "passive"))
      (node (ref "R8") (pin "1") (pinfunction "1_1") (pintype "passive"))
    )
    (net (code "97") (name "Net-(Q3-B)") (class "Default")
      (node (ref "Q3") (pin "2") (pinfunction "B_2") (pintype "passive"))
      (node (ref "R16") (pin "2") (pinfunction "2_2") (pintype "passive"))
    )
    (net (code "98") (name "Net-(Q4-B)") (class "Default")
      (node (ref "Q4") (pin "2") (pinfunction "B_2") (pintype "passive"))
      (node (ref "R17") (pin "2") (pinfunction "2_2") (pintype "passive"))
    )
    (net (code "99") (name "Net-(Q5-B)") (class "Default")
      (node (ref "Q5") (pin "1") (pinfunction "B_1") (pintype "passive"))
      (node (ref "R41") (pin "2") (pinfunction "2_2") (pintype "passive"))
    )
    (net (code "100") (name "Net-(Q6-B)") (class "Default")
      (node (ref "Q6") (pin "1") (pinfunction "B_1") (pintype "passive"))
      (node (ref "R42") (pin "2") (pinfunction "2_2") (pintype "passive"))
    )
    (net (code "101") (name "Net-(Q7-B)") (class "Default")
      (node (ref "Q7") (pin "1") (pinfunction "B_1") (pintype "passive"))
      (node (ref "R43") (pin "2") (pinfunction "2_2") (pintype "passive"))
    )
    (net (code "102") (name "Net-(U2-OSC1)") (class "Default")
      (node (ref "C21") (pin "2") (pinfunction "2_2") (pintype "passive"))
      (node (ref "U2") (pin "27") (pinfunction "OSC1_27") (pintype "input"))
      (node (ref "Y1") (pin "2") (pinfunction "OSC2_2") (pintype "passive"))
    )
    (net (code "103") (name "Net-(U2-OSC2)") (class "Default")
      (node (ref "C20") (pin "2") (pinfunction "2_2") (pintype "passive"))
      (node (ref "U2") (pin "28") (pinfunction "OSC2_28") (pintype "output"))
      (node (ref "Y1") (pin "1") (pinfunction "OSC1_1") (pintype "passive"))
    )
    (net (code "104") (name "Net-(U2-RESET)") (class "Default")
      (node (ref "C6") (pin "2") (pinfunction "2_2") (pintype "passive"))
      (node (ref "R3") (pin "2") (pinfunction "2_2") (pintype "passive"))
      (node (ref "U2") (pin "19") (pinfunction "RESET_19") (pintype "input"))
    )
    (net (code "105") (name "Net-(U5-H@2)") (class "Default")
      (node (ref "R18") (pin "2") (pinfunction "2_2") (pintype "passive"))
      (node (ref "U5") (pin "6") (pinfunction "H@2_6") (pintype "bidirectional"))
    )
    (net (code "106") (name "VBAT") (class "Default")
      (node (ref "BT1") (pin "1") (pinfunction "+_1") (pintype "passive"))
      (node (ref "C27") (pin "2") (pinfunction "2_2") (pintype "passive"))
      (node (ref "U3") (pin "1") (pinfunction "VBAT_1") (pintype "power_in"))
    )
    (net (code "107") (name "unconnected-(J3-INS-Pad9)") (class "Default")
      (node (ref "J3") (pin "9") (pinfunction "INS_9") (pintype "passive+no_connect"))
    )
    (net (code "108") (name "unconnected-(LCD1-D0-Pad7)") (class "Default")
      (node (ref "LCD1") (pin "7") (pinfunction "D0_7") (pintype "passive+no_connect"))
    )
    (net (code "109") (name "unconnected-(LCD1-D1-Pad8)") (class "Default")
      (node (ref "LCD1") (pin "8") (pinfunction "D1_8") (pintype "passive+no_connect"))
    )
    (net (code "110") (name "unconnected-(LCD1-D2-Pad9)") (class "Default")
      (node (ref "LCD1") (pin "9") (pinfunction "D2_9") (pintype "passive+no_connect"))
    )
    (net (code "111") (name "unconnected-(LCD1-D3-Pad10)") (class "Default")
      (node (ref "LCD1") (pin "10") (pinfunction "D3_10") (pintype "passive+no_connect"))
    )
    (net (code "112") (name "unconnected-(U2-CTS_N-Pad11)") (class "Default")
      (node (ref "U2") (pin "11") (pinfunction "CTS_N_11") (pintype "input+no_connect"))
    )
    (net (code "113") (name "unconnected-(U2-DCD_N-Pad10)") (class "Default")
      (node (ref "U2") (pin "10") (pinfunction "DCD_N_10") (pintype "input+no_connect"))
    )
    (net (code "114") (name "unconnected-(U2-DSR_N-Pad9)") (class "Default")
      (node (ref "U2") (pin "9") (pinfunction "DSR_N_9") (pintype "input+no_connect"))
    )
    (net (code "115") (name "unconnected-(U2-DTR_N-Pad2)") (class "Default")
      (node (ref "U2") (pin "2") (pinfunction "DTR_N_2") (pintype "output+no_connect"))
    )
    (net (code "116") (name "unconnected-(U2-EE_CLK-Pad13)") (class "Default")
      (node (ref "U2") (pin "13") (pinfunction "EE_CLK_13") (pintype "bidirectional+no_connect"))
    )
    (net (code "117") (name "unconnected-(U2-EE_DATA-Pad14)") (class "Default")
      (node (ref "U2") (pin "14") (pinfunction "EE_DATA_14") (pintype "bidirectional+no_connect"))
    )
    (net (code "118") (name "unconnected-(U2-LD_MODE-Pad23)") (class "Default")
      (node (ref "U2") (pin "23") (pinfunction "LD_MODE_23") (pintype "bidirectional+no_connect"))
    )
    (net (code "119") (name "unconnected-(U2-RI_N-Pad6)") (class "Default")
      (node (ref "U2") (pin "6") (pinfunction "RI_N_6") (pintype "input+no_connect"))
    )
    (net (code "120") (name "unconnected-(U2-RTS_N-Pad3)") (class "Default")
      (node (ref "U2") (pin "3") (pinfunction "RTS_N_3") (pintype "output+no_connect"))
    )
    (net (code "121") (name "unconnected-(U2-SHTD_N-Pad12)") (class "Default")
      (node (ref "U2") (pin "12") (pinfunction "SHTD_N_12") (pintype "output+no_connect"))
    )
    (net (code "122") (name "unconnected-(U2-TRI-MODE-Pad22)") (class "Default")
      (node (ref "U2") (pin "22") (pinfunction "TRI-MODE_22") (pintype "input+no_connect"))
    )
    (net (code "123") (name "unconnected-(U2-VDD_PLL-Pad24)") (class "Default")
      (node (ref "U2") (pin "24") (pinfunction "VDD_PLL_24") (pintype "power_in+no_connect"))
    )
    (net (code "124") (name "unconnected-(U3A-PB12-Pad33)") (class "Default")
      (node (ref "U3") (pin "33") (pinfunction "PB12_33") (pintype "bidirectional"))
    )
    (net (code "125") (name "unconnected-(U3A-PB13-Pad34)") (class "Default")
      (node (ref "U3") (pin "34") (pinfunction "PB13_34") (pintype "bidirectional"))
    )
    (net (code "126") (name "unconnected-(U3A-PB14-Pad35)") (class "Default")
      (node (ref "U3") (pin "35") (pinfunction "PB14_35") (pintype "bidirectional"))
    )
    (net (code "127") (name "unconnected-(U3A-PB15-Pad36)") (class "Default")
      (node (ref "U3") (pin "36") (pinfunction "PB15_36") (pintype "bidirectional"))
    )
    (net (code "128") (name "unconnected-(U3A-PC3-Pad11)") (class "Default")
      (node (ref "U3") (pin "11") (pinfunction "PC3_11") (pintype "bidirectional"))
    )
    (net (code "129") (name "unconnected-(U3A-PC4-Pad24)") (class "Default")
      (node (ref "U3") (pin "24") (pinfunction "PC4_24") (pintype "bidirectional"))
    )
    (net (code "130") (name "unconnected-(U3A-PC5-Pad25)") (class "Default")
      (node (ref "U3") (pin "25") (pinfunction "PC5_25") (pintype "bidirectional"))
    )
    (net (code "131") (name "unconnected-(U3A-PC6-Pad37)") (class "Default")
      (node (ref "U3") (pin "37") (pinfunction "PC6_37") (pintype "bidirectional"))
    )
    (net (code "132") (name "unconnected-(U3A-PC7-Pad38)") (class "Default")
      (node (ref "U3") (pin "38") (pinfunction "PC7_38") (pintype "bidirectional"))
    )
    (net (code "133") (name "unconnected-(U3A-PC13-TAMPER-RTC-Pad2)") (class "Default")
      (node (ref "U3") (pin "2") (pinfunction "PC13-TAMPER-RTC_2") (pintype "bidirectional"))
    )
    (net (code "134") (name "unconnected-(U6-NC-Pad3)") (class "Default")
      (node (ref "U6") (pin "3") (pinfunction "NC_3") (pintype "passive+no_connect"))
    )
  )
)
